# MainBoardRev2.net
KiCad netlist of a schematic drawn in EAGLE
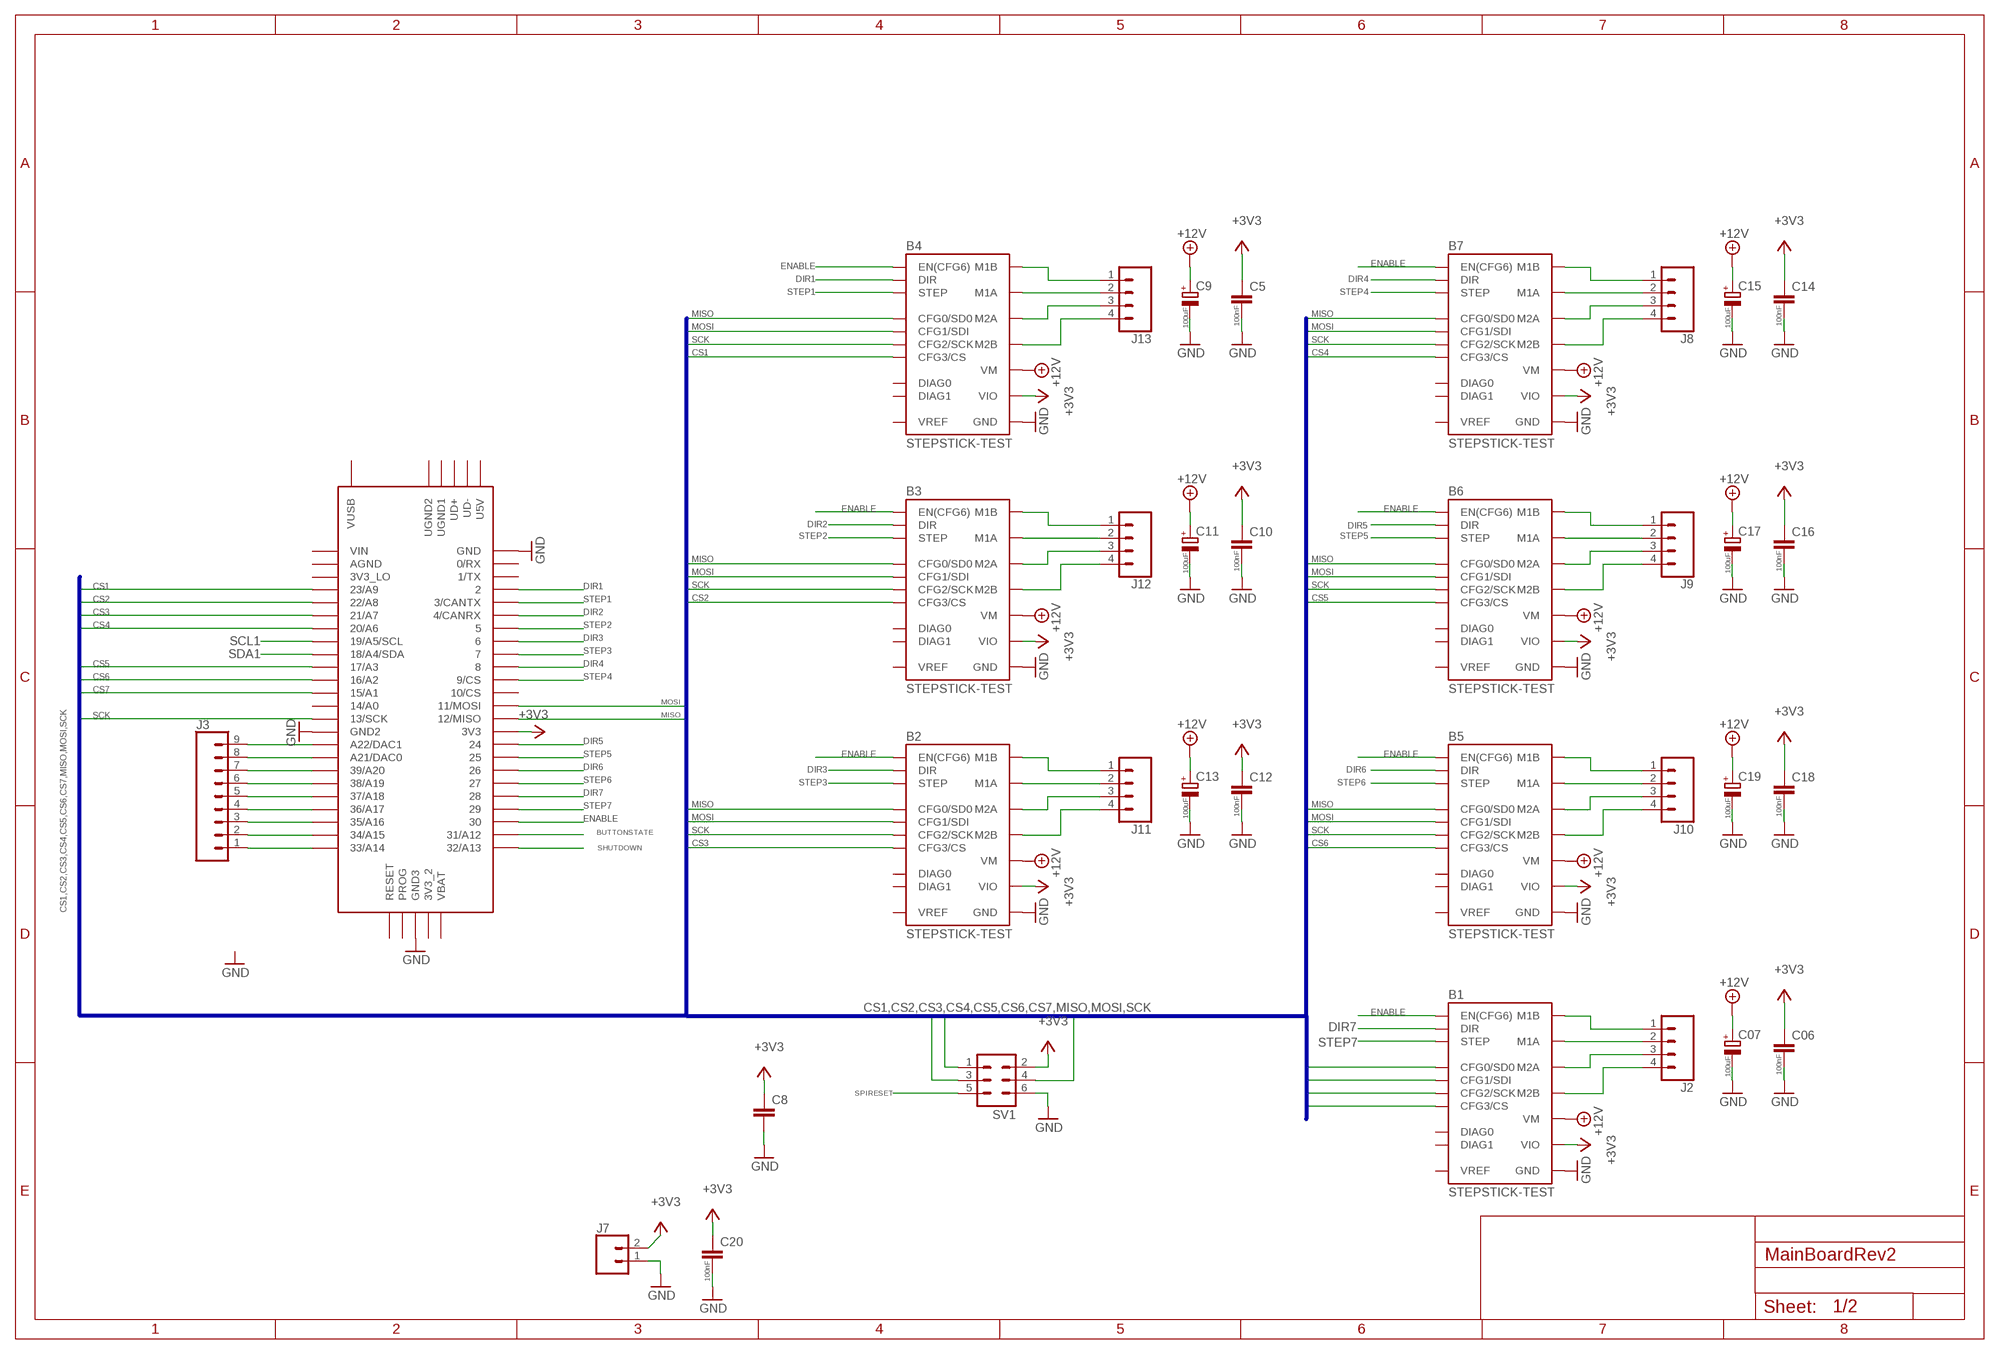
[diagram p0: schematic, sheet 1]
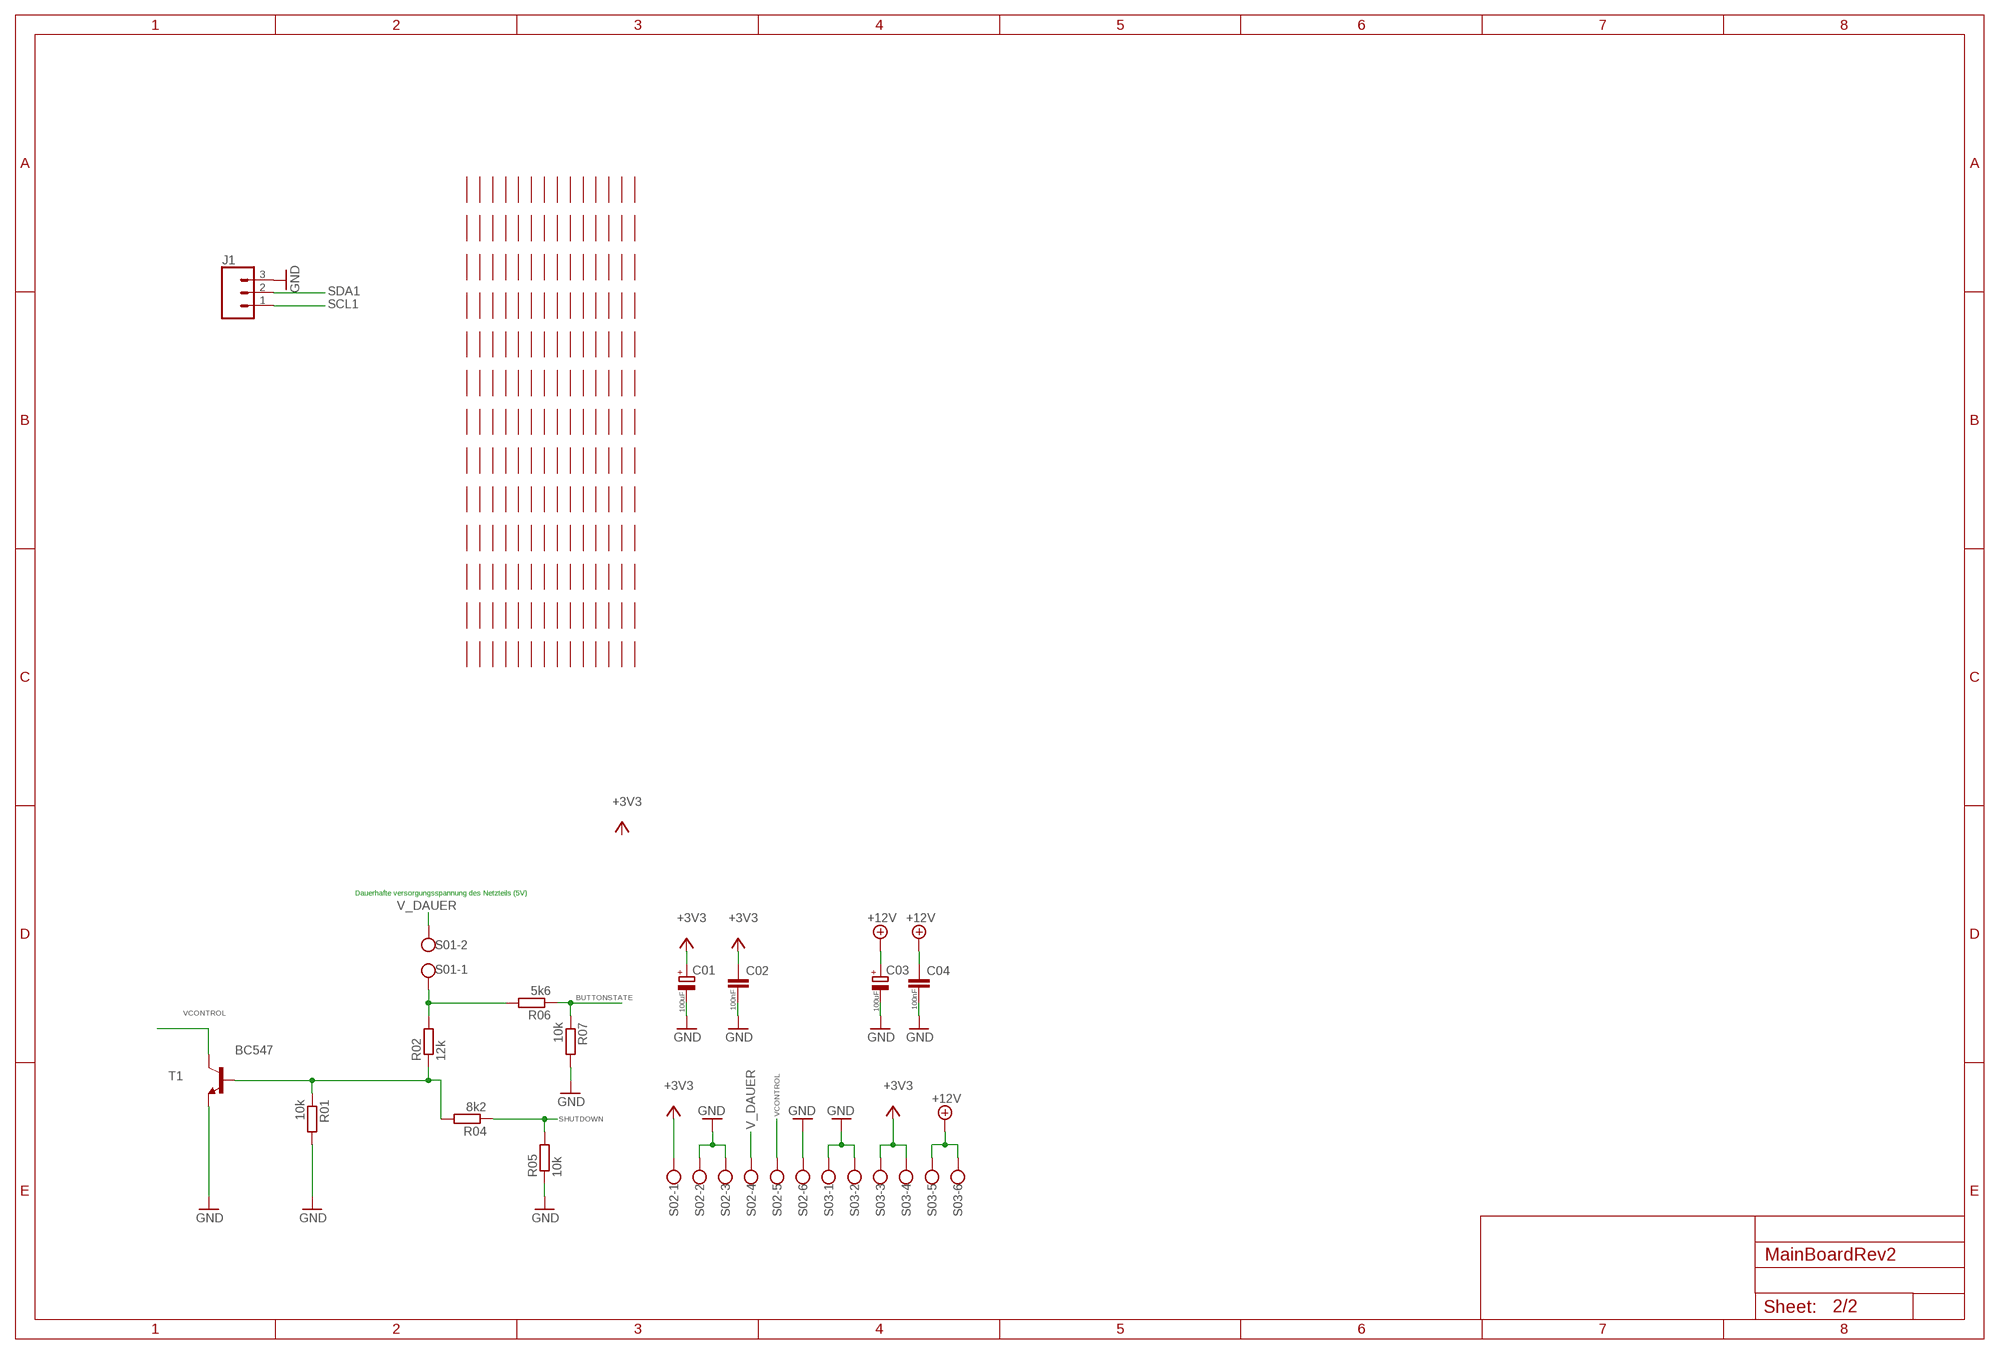
[diagram p1: schematic, sheet 2]

(export (version "E")
  (design (tool "Eeschema 10.0.6"))
  (components
    (comp (ref "C01")
      (value "100uF")
      (footprint "eagle-import:E2,5-6")
      (libsource (lib "eagle-import") (part "CPOL-EUE2.5-6"))
    )
    (comp (ref "C02")
      (value "100nF")
      (footprint "eagle-import:C050-024X044")
      (libsource (lib "eagle-import") (part "C-EU050-024X044"))
    )
    (comp (ref "C03")
      (value "100uF")
      (footprint "eagle-import:E2,5-6")
      (libsource (lib "eagle-import") (part "CPOL-EUE2.5-6"))
    )
    (comp (ref "C04")
      (value "100nF")
      (footprint "eagle-import:C050-024X044")
      (libsource (lib "eagle-import") (part "C-EU050-024X044"))
    )
    (comp (ref "J1")
      (value "CONN_03LONGPADS")
      (footprint "eagle-import:1X03_LONGPADS")
      (libsource (lib "eagle-import") (part "CONN_03LONGPADS"))
    )
    (comp (ref "R01")
      (value "10k")
      (footprint "eagle-import:0207_10")
      (libsource (lib "eagle-import") (part "R-EU_0207/10"))
    )
    (comp (ref "R02")
      (value "12k")
      (footprint "eagle-import:0207_10")
      (libsource (lib "eagle-import") (part "R-EU_0207/10"))
    )
    (comp (ref "R04")
      (value "8k2")
      (footprint "eagle-import:0207_10")
      (libsource (lib "eagle-import") (part "R-EU_0207/10"))
    )
    (comp (ref "R05")
      (value "10k")
      (footprint "eagle-import:0207_10")
      (libsource (lib "eagle-import") (part "R-EU_0207/10"))
    )
    (comp (ref "R06")
      (value "5k6")
      (footprint "eagle-import:0207_10")
      (libsource (lib "eagle-import") (part "R-EU_0207/10"))
    )
    (comp (ref "R07")
      (value "10k")
      (footprint "eagle-import:0207_10")
      (libsource (lib "eagle-import") (part "R-EU_0207/10"))
    )
    (comp (ref "S01")
      (value "W237-102")
      (footprint "eagle-import:W237-102")
      (fields (field (name "MPN") "237-102"))
      (libsource (lib "eagle-import") (part "W237-102"))
    )
    (comp (ref "S02")
      (value "W237-6")
      (footprint "eagle-import:W237-6")
      (libsource (lib "eagle-import") (part "W237-6"))
    )
    (comp (ref "S03")
      (value "W237-6")
      (footprint "eagle-import:W237-6")
      (libsource (lib "eagle-import") (part "W237-6"))
    )
    (comp (ref "T1")
      (value "BC547")
      (footprint "eagle-import:TO92")
      (libsource (lib "eagle-import") (part "BC547"))
    )
    (comp (ref "U$2")
      (value "LOCHRASTER")
      (footprint "eagle-import:LOCHRASTER")
      (libsource (lib "eagle-import") (part "LOCHRASTER"))
    )
    (comp (ref "B1")
      (value "STEPSTICK-TEST")
      (footprint "eagle-import:STEPSTICK-TEST")
      (libsource (lib "eagle-import") (part "STEPSTICK-TEST"))
    )
    (comp (ref "B2")
      (value "STEPSTICK-TEST")
      (footprint "eagle-import:STEPSTICK-TEST")
      (libsource (lib "eagle-import") (part "STEPSTICK-TEST"))
    )
    (comp (ref "B3")
      (value "STEPSTICK-TEST")
      (footprint "eagle-import:STEPSTICK-TEST")
      (libsource (lib "eagle-import") (part "STEPSTICK-TEST"))
    )
    (comp (ref "B4")
      (value "STEPSTICK-TEST")
      (footprint "eagle-import:STEPSTICK-TEST")
      (libsource (lib "eagle-import") (part "STEPSTICK-TEST"))
    )
    (comp (ref "B5")
      (value "STEPSTICK-TEST")
      (footprint "eagle-import:STEPSTICK-TEST")
      (libsource (lib "eagle-import") (part "STEPSTICK-TEST"))
    )
    (comp (ref "B6")
      (value "STEPSTICK-TEST")
      (footprint "eagle-import:STEPSTICK-TEST")
      (libsource (lib "eagle-import") (part "STEPSTICK-TEST"))
    )
    (comp (ref "B7")
      (value "STEPSTICK-TEST")
      (footprint "eagle-import:STEPSTICK-TEST")
      (libsource (lib "eagle-import") (part "STEPSTICK-TEST"))
    )
    (comp (ref "C5")
      (value "100nF")
      (footprint "eagle-import:C050-024X044")
      (libsource (lib "eagle-import") (part "C-EU050-024X044"))
    )
    (comp (ref "C06")
      (value "100nF")
      (footprint "eagle-import:C050-024X044")
      (libsource (lib "eagle-import") (part "C-EU050-024X044"))
    )
    (comp (ref "C07")
      (value "100uF")
      (footprint "eagle-import:E2,5-6")
      (libsource (lib "eagle-import") (part "CPOL-EUE2.5-6"))
    )
    (comp (ref "C8")
      (value "C-EU050-024X044")
      (footprint "eagle-import:C050-024X044")
      (libsource (lib "eagle-import") (part "C-EU050-024X044"))
    )
    (comp (ref "C9")
      (value "100uF")
      (footprint "eagle-import:E2,5-6")
      (libsource (lib "eagle-import") (part "CPOL-EUE2.5-6"))
    )
    (comp (ref "C10")
      (value "100nF")
      (footprint "eagle-import:C050-024X044")
      (libsource (lib "eagle-import") (part "C-EU050-024X044"))
    )
    (comp (ref "C11")
      (value "100uF")
      (footprint "eagle-import:E2,5-6")
      (libsource (lib "eagle-import") (part "CPOL-EUE2.5-6"))
    )
    (comp (ref "C12")
      (value "100nF")
      (footprint "eagle-import:C050-024X044")
      (libsource (lib "eagle-import") (part "C-EU050-024X044"))
    )
    (comp (ref "C13")
      (value "100uF")
      (footprint "eagle-import:E2,5-6")
      (libsource (lib "eagle-import") (part "CPOL-EUE2.5-6"))
    )
    (comp (ref "C14")
      (value "100nF")
      (footprint "eagle-import:C050-024X044")
      (libsource (lib "eagle-import") (part "C-EU050-024X044"))
    )
    (comp (ref "C15")
      (value "100uF")
      (footprint "eagle-import:E2,5-6")
      (libsource (lib "eagle-import") (part "CPOL-EUE2.5-6"))
    )
    (comp (ref "C16")
      (value "100nF")
      (footprint "eagle-import:C050-024X044")
      (libsource (lib "eagle-import") (part "C-EU050-024X044"))
    )
    (comp (ref "C17")
      (value "100uF")
      (footprint "eagle-import:E2,5-6")
      (libsource (lib "eagle-import") (part "CPOL-EUE2.5-6"))
    )
    (comp (ref "C18")
      (value "100nF")
      (footprint "eagle-import:C050-024X044")
      (libsource (lib "eagle-import") (part "C-EU050-024X044"))
    )
    (comp (ref "C19")
      (value "100uF")
      (footprint "eagle-import:E2,5-6")
      (libsource (lib "eagle-import") (part "CPOL-EUE2.5-6"))
    )
    (comp (ref "C20")
      (value "100nF")
      (footprint "eagle-import:C050-024X044")
      (libsource (lib "eagle-import") (part "C-EU050-024X044"))
    )
    (comp (ref "J2")
      (value "CONN_041X04_NO_SILK")
      (footprint "eagle-import:1X04_NO_SILK")
      (libsource (lib "eagle-import") (part "CONN_041X04_NO_SILK"))
    )
    (comp (ref "J3")
      (value "CONN_09LONGPADS")
      (footprint "eagle-import:1X09_LONGPADS")
      (libsource (lib "eagle-import") (part "CONN_09LONGPADS"))
    )
    (comp (ref "J7")
      (value "CONN_02PTH3")
      (footprint "eagle-import:1X02_LONGPADS")
      (libsource (lib "eagle-import") (part "CONN_02PTH3"))
    )
    (comp (ref "J8")
      (value "CONN_041X04_NO_SILK")
      (footprint "eagle-import:1X04_NO_SILK")
      (libsource (lib "eagle-import") (part "CONN_041X04_NO_SILK"))
    )
    (comp (ref "J9")
      (value "CONN_041X04_NO_SILK")
      (footprint "eagle-import:1X04_NO_SILK")
      (libsource (lib "eagle-import") (part "CONN_041X04_NO_SILK"))
    )
    (comp (ref "J10")
      (value "CONN_041X04_NO_SILK")
      (footprint "eagle-import:1X04_NO_SILK")
      (libsource (lib "eagle-import") (part "CONN_041X04_NO_SILK"))
    )
    (comp (ref "J11")
      (value "CONN_041X04_NO_SILK")
      (footprint "eagle-import:1X04_NO_SILK")
      (libsource (lib "eagle-import") (part "CONN_041X04_NO_SILK"))
    )
    (comp (ref "J12")
      (value "CONN_041X04_NO_SILK")
      (footprint "eagle-import:1X04_NO_SILK")
      (libsource (lib "eagle-import") (part "CONN_041X04_NO_SILK"))
    )
    (comp (ref "J13")
      (value "CONN_041X04_NO_SILK")
      (footprint "eagle-import:1X04_NO_SILK")
      (libsource (lib "eagle-import") (part "CONN_041X04_NO_SILK"))
    )
    (comp (ref "SV1")
      (value "MA03-2")
      (footprint "eagle-import:MA03-2")
      (libsource (lib "eagle-import") (part "MA03-2"))
    )
    (comp (ref "U$1")
      (value "TEENSY_4.1")
      (footprint "eagle-import:TEENSY_4.1")
      (libsource (lib "eagle-import") (part "TEENSY_4.1"))
    )
  )
  (nets
    (net (code "1") (name "+3V3") (class "Default")
      (node (ref "B1") (pin "VIO") (pinfunction "VIO_VIO") (pintype "power_in"))
      (node (ref "B2") (pin "VIO") (pinfunction "VIO_VIO") (pintype "power_in"))
      (node (ref "B3") (pin "VIO") (pinfunction "VIO_VIO") (pintype "power_in"))
      (node (ref "B4") (pin "VIO") (pinfunction "VIO_VIO") (pintype "power_in"))
      (node (ref "B5") (pin "VIO") (pinfunction "VIO_VIO") (pintype "power_in"))
      (node (ref "B6") (pin "VIO") (pinfunction "VIO_VIO") (pintype "power_in"))
      (node (ref "B7") (pin "VIO") (pinfunction "VIO_VIO") (pintype "power_in"))
      (node (ref "C01") (pin "+") (pinfunction "+_+") (pintype "passive"))
      (node (ref "C02") (pin "1") (pinfunction "1_1") (pintype "passive"))
      (node (ref "C06") (pin "1") (pinfunction "1_1") (pintype "passive"))
      (node (ref "C10") (pin "1") (pinfunction "1_1") (pintype "passive"))
      (node (ref "C12") (pin "1") (pinfunction "1_1") (pintype "passive"))
      (node (ref "C14") (pin "1") (pinfunction "1_1") (pintype "passive"))
      (node (ref "C16") (pin "1") (pinfunction "1_1") (pintype "passive"))
      (node (ref "C18") (pin "1") (pinfunction "1_1") (pintype "passive"))
      (node (ref "C20") (pin "1") (pinfunction "1_1") (pintype "passive"))
      (node (ref "C5") (pin "1") (pinfunction "1_1") (pintype "passive"))
      (node (ref "C8") (pin "1") (pinfunction "1_1") (pintype "passive"))
      (node (ref "J7") (pin "2") (pinfunction "2_2") (pintype "passive"))
      (node (ref "S02") (pin "1") (pinfunction "KL_1") (pintype "passive"))
      (node (ref "S03") (pin "3") (pinfunction "KL_3") (pintype "passive"))
      (node (ref "S03") (pin "4") (pinfunction "KL_4") (pintype "passive"))
      (node (ref "SV1") (pin "2") (pinfunction "2_2") (pintype "passive"))
      (node (ref "U$1") (pin "3V3") (pinfunction "3V3_3V3") (pintype "bidirectional"))
    )
    (net (code "2") (name "+12V") (class "Default")
      (node (ref "B1") (pin "VM") (pinfunction "VM_VM") (pintype "power_in"))
      (node (ref "B2") (pin "VM") (pinfunction "VM_VM") (pintype "power_in"))
      (node (ref "B3") (pin "VM") (pinfunction "VM_VM") (pintype "power_in"))
      (node (ref "B4") (pin "VM") (pinfunction "VM_VM") (pintype "power_in"))
      (node (ref "B5") (pin "VM") (pinfunction "VM_VM") (pintype "power_in"))
      (node (ref "B6") (pin "VM") (pinfunction "VM_VM") (pintype "power_in"))
      (node (ref "B7") (pin "VM") (pinfunction "VM_VM") (pintype "power_in"))
      (node (ref "C03") (pin "+") (pinfunction "+_+") (pintype "passive"))
      (node (ref "C04") (pin "1") (pinfunction "1_1") (pintype "passive"))
      (node (ref "C07") (pin "+") (pinfunction "+_+") (pintype "passive"))
      (node (ref "C11") (pin "+") (pinfunction "+_+") (pintype "passive"))
      (node (ref "C13") (pin "+") (pinfunction "+_+") (pintype "passive"))
      (node (ref "C15") (pin "+") (pinfunction "+_+") (pintype "passive"))
      (node (ref "C17") (pin "+") (pinfunction "+_+") (pintype "passive"))
      (node (ref "C19") (pin "+") (pinfunction "+_+") (pintype "passive"))
      (node (ref "C9") (pin "+") (pinfunction "+_+") (pintype "passive"))
      (node (ref "S03") (pin "5") (pinfunction "KL_5") (pintype "passive"))
      (node (ref "S03") (pin "6") (pinfunction "KL_6") (pintype "passive"))
    )
    (net (code "4") (name "BUTTONSTATE") (class "Default")
      (node (ref "R06") (pin "1") (pinfunction "1_1") (pintype "passive"))
      (node (ref "R07") (pin "1") (pinfunction "1_1") (pintype "passive"))
      (node (ref "U$1") (pin "31/A12") (pinfunction "31/A12_31/A12") (pintype "bidirectional"))
    )
    (net (code "5") (name "CS1") (class "Default")
      (node (ref "B4") (pin "CFG3") (pinfunction "CFG3/CS_CFG3") (pintype "bidirectional"))
      (node (ref "U$1") (pin "23/A9") (pinfunction "23/A9_23/A9") (pintype "bidirectional"))
    )
    (net (code "6") (name "CS2") (class "Default")
      (node (ref "B3") (pin "CFG3") (pinfunction "CFG3/CS_CFG3") (pintype "bidirectional"))
      (node (ref "U$1") (pin "22/A8") (pinfunction "22/A8_22/A8") (pintype "bidirectional"))
    )
    (net (code "7") (name "CS3") (class "Default")
      (node (ref "B2") (pin "CFG3") (pinfunction "CFG3/CS_CFG3") (pintype "bidirectional"))
      (node (ref "U$1") (pin "21/A7") (pinfunction "21/A7_21/A7") (pintype "bidirectional"))
    )
    (net (code "8") (name "CS4") (class "Default")
      (node (ref "B7") (pin "CFG3") (pinfunction "CFG3/CS_CFG3") (pintype "bidirectional"))
      (node (ref "U$1") (pin "20/A6") (pinfunction "20/A6_20/A6") (pintype "bidirectional"))
    )
    (net (code "9") (name "CS5") (class "Default")
      (node (ref "B6") (pin "CFG3") (pinfunction "CFG3/CS_CFG3") (pintype "bidirectional"))
      (node (ref "U$1") (pin "17/A3") (pinfunction "17/A3_17/A3") (pintype "bidirectional"))
    )
    (net (code "10") (name "CS6") (class "Default")
      (node (ref "B5") (pin "CFG3") (pinfunction "CFG3/CS_CFG3") (pintype "bidirectional"))
      (node (ref "U$1") (pin "16/A2") (pinfunction "16/A2_16/A2") (pintype "bidirectional"))
    )
    (net (code "11") (name "CS7") (class "Default")
      (node (ref "B1") (pin "CFG3") (pinfunction "CFG3/CS_CFG3") (pintype "bidirectional"))
      (node (ref "U$1") (pin "15/A1") (pinfunction "15/A1_15/A1") (pintype "bidirectional"))
    )
    (net (code "12") (name "DIR1") (class "Default")
      (node (ref "B4") (pin "DIR") (pinfunction "DIR_DIR") (pintype "bidirectional"))
      (node (ref "U$1") (pin "2") (pinfunction "2_2") (pintype "bidirectional"))
    )
    (net (code "13") (name "DIR2") (class "Default")
      (node (ref "B3") (pin "DIR") (pinfunction "DIR_DIR") (pintype "bidirectional"))
      (node (ref "U$1") (pin "4/CANRX") (pinfunction "4/CANRX_4/CANRX") (pintype "bidirectional"))
    )
    (net (code "14") (name "DIR3") (class "Default")
      (node (ref "B2") (pin "DIR") (pinfunction "DIR_DIR") (pintype "bidirectional"))
      (node (ref "U$1") (pin "6") (pinfunction "6_6") (pintype "bidirectional"))
    )
    (net (code "15") (name "DIR4") (class "Default")
      (node (ref "B7") (pin "DIR") (pinfunction "DIR_DIR") (pintype "bidirectional"))
      (node (ref "U$1") (pin "8") (pinfunction "8_8") (pintype "bidirectional"))
    )
    (net (code "16") (name "DIR5") (class "Default")
      (node (ref "B6") (pin "DIR") (pinfunction "DIR_DIR") (pintype "bidirectional"))
      (node (ref "U$1") (pin "24/A10") (pinfunction "24_24/A10") (pintype "bidirectional"))
    )
    (net (code "17") (name "DIR6") (class "Default")
      (node (ref "B5") (pin "DIR") (pinfunction "DIR_DIR") (pintype "bidirectional"))
      (node (ref "U$1") (pin "26/12") (pinfunction "26_26/12") (pintype "bidirectional"))
    )
    (net (code "18") (name "DIR7") (class "Default")
      (node (ref "B1") (pin "DIR") (pinfunction "DIR_DIR") (pintype "bidirectional"))
      (node (ref "U$1") (pin "28") (pinfunction "28_28") (pintype "bidirectional"))
    )
    (net (code "19") (name "ENABLE") (class "Default")
      (node (ref "B1") (pin "EN") (pinfunction "EN(CFG6)_EN") (pintype "bidirectional"))
      (node (ref "B2") (pin "EN") (pinfunction "EN(CFG6)_EN") (pintype "bidirectional"))
      (node (ref "B3") (pin "EN") (pinfunction "EN(CFG6)_EN") (pintype "bidirectional"))
      (node (ref "B4") (pin "EN") (pinfunction "EN(CFG6)_EN") (pintype "bidirectional"))
      (node (ref "B5") (pin "EN") (pinfunction "EN(CFG6)_EN") (pintype "bidirectional"))
      (node (ref "B6") (pin "EN") (pinfunction "EN(CFG6)_EN") (pintype "bidirectional"))
      (node (ref "B7") (pin "EN") (pinfunction "EN(CFG6)_EN") (pintype "bidirectional"))
      (node (ref "U$1") (pin "30") (pinfunction "30_30") (pintype "bidirectional"))
    )
    (net (code "20") (name "GND") (class "Default")
      (node (ref "B1") (pin "GND@1") (pinfunction "GND_GND@1") (pintype "power_in"))
      (node (ref "B1") (pin "GND@2") (pinfunction "GND_GND@2") (pintype "power_in"))
      (node (ref "B2") (pin "GND@1") (pinfunction "GND_GND@1") (pintype "power_in"))
      (node (ref "B2") (pin "GND@2") (pinfunction "GND_GND@2") (pintype "power_in"))
      (node (ref "B3") (pin "GND@1") (pinfunction "GND_GND@1") (pintype "power_in"))
      (node (ref "B3") (pin "GND@2") (pinfunction "GND_GND@2") (pintype "power_in"))
      (node (ref "B4") (pin "GND@1") (pinfunction "GND_GND@1") (pintype "power_in"))
      (node (ref "B4") (pin "GND@2") (pinfunction "GND_GND@2") (pintype "power_in"))
      (node (ref "B5") (pin "GND@1") (pinfunction "GND_GND@1") (pintype "power_in"))
      (node (ref "B5") (pin "GND@2") (pinfunction "GND_GND@2") (pintype "power_in"))
      (node (ref "B6") (pin "GND@1") (pinfunction "GND_GND@1") (pintype "power_in"))
      (node (ref "B6") (pin "GND@2") (pinfunction "GND_GND@2") (pintype "power_in"))
      (node (ref "B7") (pin "GND@1") (pinfunction "GND_GND@1") (pintype "power_in"))
      (node (ref "B7") (pin "GND@2") (pinfunction "GND_GND@2") (pintype "power_in"))
      (node (ref "C01") (pin "-") (pinfunction "-_-") (pintype "passive"))
      (node (ref "C02") (pin "2") (pinfunction "2_2") (pintype "passive"))
      (node (ref "C03") (pin "-") (pinfunction "-_-") (pintype "passive"))
      (node (ref "C04") (pin "2") (pinfunction "2_2") (pintype "passive"))
      (node (ref "C06") (pin "2") (pinfunction "2_2") (pintype "passive"))
      (node (ref "C07") (pin "-") (pinfunction "-_-") (pintype "passive"))
      (node (ref "C10") (pin "2") (pinfunction "2_2") (pintype "passive"))
      (node (ref "C11") (pin "-") (pinfunction "-_-") (pintype "passive"))
      (node (ref "C12") (pin "2") (pinfunction "2_2") (pintype "passive"))
      (node (ref "C13") (pin "-") (pinfunction "-_-") (pintype "passive"))
      (node (ref "C14") (pin "2") (pinfunction "2_2") (pintype "passive"))
      (node (ref "C15") (pin "-") (pinfunction "-_-") (pintype "passive"))
      (node (ref "C16") (pin "2") (pinfunction "2_2") (pintype "passive"))
      (node (ref "C17") (pin "-") (pinfunction "-_-") (pintype "passive"))
      (node (ref "C18") (pin "2") (pinfunction "2_2") (pintype "passive"))
      (node (ref "C19") (pin "-") (pinfunction "-_-") (pintype "passive"))
      (node (ref "C20") (pin "2") (pinfunction "2_2") (pintype "passive"))
      (node (ref "C5") (pin "2") (pinfunction "2_2") (pintype "passive"))
      (node (ref "C8") (pin "2") (pinfunction "2_2") (pintype "passive"))
      (node (ref "C9") (pin "-") (pinfunction "-_-") (pintype "passive"))
      (node (ref "J1") (pin "3") (pinfunction "3_3") (pintype "passive"))
      (node (ref "J7") (pin "1") (pinfunction "1_1") (pintype "passive"))
      (node (ref "R01") (pin "2") (pinfunction "2_2") (pintype "passive"))
      (node (ref "R05") (pin "1") (pinfunction "1_1") (pintype "passive"))
      (node (ref "R07") (pin "2") (pinfunction "2_2") (pintype "passive"))
      (node (ref "S02") (pin "2") (pinfunction "KL_2") (pintype "passive"))
      (node (ref "S02") (pin "3") (pinfunction "KL_3") (pintype "passive"))
      (node (ref "S02") (pin "6") (pinfunction "KL_6") (pintype "passive"))
      (node (ref "S03") (pin "1") (pinfunction "KL_1") (pintype "passive"))
      (node (ref "S03") (pin "2") (pinfunction "KL_2") (pintype "passive"))
      (node (ref "SV1") (pin "6") (pinfunction "6_6") (pintype "passive"))
      (node (ref "T1") (pin "1") (pinfunction "E_1") (pintype "passive"))
      (node (ref "U$1") (pin "GND") (pinfunction "GND_GND") (pintype "bidirectional"))
      (node (ref "U$1") (pin "GND2") (pinfunction "GND2_GND2") (pintype "bidirectional"))
      (node (ref "U$1") (pin "GND3") (pinfunction "GND3_GND3") (pintype "bidirectional"))
    )
    (net (code "21") (name "MISO") (class "Default")
      (node (ref "B1") (pin "NC/CFG0") (pinfunction "CFG0/SD0_NC/CFG0") (pintype "bidirectional"))
      (node (ref "B2") (pin "NC/CFG0") (pinfunction "CFG0/SD0_NC/CFG0") (pintype "bidirectional"))
      (node (ref "B3") (pin "NC/CFG0") (pinfunction "CFG0/SD0_NC/CFG0") (pintype "bidirectional"))
      (node (ref "B4") (pin "NC/CFG0") (pinfunction "CFG0/SD0_NC/CFG0") (pintype "bidirectional"))
      (node (ref "B5") (pin "NC/CFG0") (pinfunction "CFG0/SD0_NC/CFG0") (pintype "bidirectional"))
      (node (ref "B6") (pin "NC/CFG0") (pinfunction "CFG0/SD0_NC/CFG0") (pintype "bidirectional"))
      (node (ref "B7") (pin "NC/CFG0") (pinfunction "CFG0/SD0_NC/CFG0") (pintype "bidirectional"))
      (node (ref "SV1") (pin "1") (pinfunction "1_1") (pintype "passive"))
      (node (ref "U$1") (pin "12/MISO") (pinfunction "12/MISO_12/MISO") (pintype "bidirectional"))
    )
    (net (code "22") (name "MOSI") (class "Default")
      (node (ref "B1") (pin "CFG1") (pinfunction "CFG1/SDI_CFG1") (pintype "bidirectional"))
      (node (ref "B2") (pin "CFG1") (pinfunction "CFG1/SDI_CFG1") (pintype "bidirectional"))
      (node (ref "B3") (pin "CFG1") (pinfunction "CFG1/SDI_CFG1") (pintype "bidirectional"))
      (node (ref "B4") (pin "CFG1") (pinfunction "CFG1/SDI_CFG1") (pintype "bidirectional"))
      (node (ref "B5") (pin "CFG1") (pinfunction "CFG1/SDI_CFG1") (pintype "bidirectional"))
      (node (ref "B6") (pin "CFG1") (pinfunction "CFG1/SDI_CFG1") (pintype "bidirectional"))
      (node (ref "B7") (pin "CFG1") (pinfunction "CFG1/SDI_CFG1") (pintype "bidirectional"))
      (node (ref "SV1") (pin "4") (pinfunction "4_4") (pintype "passive"))
      (node (ref "U$1") (pin "11/MOSI") (pinfunction "11/MOSI_11/MOSI") (pintype "bidirectional"))
    )
    (net (code "23") (name "Net-(B1-PadM1A)") (class "Default")
      (node (ref "B1") (pin "M1A") (pinfunction "M1A_M1A") (pintype "output"))
      (node (ref "J2") (pin "2") (pinfunction "2_2") (pintype "passive"))
    )
    (net (code "24") (name "Net-(B1-PadM1B)") (class "Default")
      (node (ref "B1") (pin "M1B") (pinfunction "M1B_M1B") (pintype "output"))
      (node (ref "J2") (pin "1") (pinfunction "1_1") (pintype "passive"))
    )
    (net (code "25") (name "Net-(B1-PadM2A)") (class "Default")
      (node (ref "B1") (pin "M2A") (pinfunction "M2A_M2A") (pintype "output"))
      (node (ref "J2") (pin "3") (pinfunction "3_3") (pintype "passive"))
    )
    (net (code "26") (name "Net-(B1-PadM2B)") (class "Default")
      (node (ref "B1") (pin "M2B") (pinfunction "M2B_M2B") (pintype "output"))
      (node (ref "J2") (pin "4") (pinfunction "4_4") (pintype "passive"))
    )
    (net (code "27") (name "Net-(B2-PadM1A)") (class "Default")
      (node (ref "B2") (pin "M1A") (pinfunction "M1A_M1A") (pintype "output"))
      (node (ref "J11") (pin "2") (pinfunction "2_2") (pintype "passive"))
    )
    (net (code "28") (name "Net-(B2-PadM1B)") (class "Default")
      (node (ref "B2") (pin "M1B") (pinfunction "M1B_M1B") (pintype "output"))
      (node (ref "J11") (pin "1") (pinfunction "1_1") (pintype "passive"))
    )
    (net (code "29") (name "Net-(B2-PadM2A)") (class "Default")
      (node (ref "B2") (pin "M2A") (pinfunction "M2A_M2A") (pintype "output"))
      (node (ref "J11") (pin "3") (pinfunction "3_3") (pintype "passive"))
    )
    (net (code "30") (name "Net-(B2-PadM2B)") (class "Default")
      (node (ref "B2") (pin "M2B") (pinfunction "M2B_M2B") (pintype "output"))
      (node (ref "J11") (pin "4") (pinfunction "4_4") (pintype "passive"))
    )
    (net (code "31") (name "Net-(B3-PadM1A)") (class "Default")
      (node (ref "B3") (pin "M1A") (pinfunction "M1A_M1A") (pintype "output"))
      (node (ref "J12") (pin "2") (pinfunction "2_2") (pintype "passive"))
    )
    (net (code "32") (name "Net-(B3-PadM1B)") (class "Default")
      (node (ref "B3") (pin "M1B") (pinfunction "M1B_M1B") (pintype "output"))
      (node (ref "J12") (pin "1") (pinfunction "1_1") (pintype "passive"))
    )
    (net (code "33") (name "Net-(B3-PadM2A)") (class "Default")
      (node (ref "B3") (pin "M2A") (pinfunction "M2A_M2A") (pintype "output"))
      (node (ref "J12") (pin "3") (pinfunction "3_3") (pintype "passive"))
    )
    (net (code "34") (name "Net-(B3-PadM2B)") (class "Default")
      (node (ref "B3") (pin "M2B") (pinfunction "M2B_M2B") (pintype "output"))
      (node (ref "J12") (pin "4") (pinfunction "4_4") (pintype "passive"))
    )
    (net (code "35") (name "Net-(B4-PadM1A)") (class "Default")
      (node (ref "B4") (pin "M1A") (pinfunction "M1A_M1A") (pintype "output"))
      (node (ref "J13") (pin "2") (pinfunction "2_2") (pintype "passive"))
    )
    (net (code "36") (name "Net-(B4-PadM1B)") (class "Default")
      (node (ref "B4") (pin "M1B") (pinfunction "M1B_M1B") (pintype "output"))
      (node (ref "J13") (pin "1") (pinfunction "1_1") (pintype "passive"))
    )
    (net (code "37") (name "Net-(B4-PadM2A)") (class "Default")
      (node (ref "B4") (pin "M2A") (pinfunction "M2A_M2A") (pintype "output"))
      (node (ref "J13") (pin "3") (pinfunction "3_3") (pintype "passive"))
    )
    (net (code "38") (name "Net-(B4-PadM2B)") (class "Default")
      (node (ref "B4") (pin "M2B") (pinfunction "M2B_M2B") (pintype "output"))
      (node (ref "J13") (pin "4") (pinfunction "4_4") (pintype "passive"))
    )
    (net (code "39") (name "Net-(B5-PadM1A)") (class "Default")
      (node (ref "B5") (pin "M1A") (pinfunction "M1A_M1A") (pintype "output"))
      (node (ref "J10") (pin "2") (pinfunction "2_2") (pintype "passive"))
    )
    (net (code "40") (name "Net-(B5-PadM1B)") (class "Default")
      (node (ref "B5") (pin "M1B") (pinfunction "M1B_M1B") (pintype "output"))
      (node (ref "J10") (pin "1") (pinfunction "1_1") (pintype "passive"))
    )
    (net (code "41") (name "Net-(B5-PadM2A)") (class "Default")
      (node (ref "B5") (pin "M2A") (pinfunction "M2A_M2A") (pintype "output"))
      (node (ref "J10") (pin "3") (pinfunction "3_3") (pintype "passive"))
    )
    (net (code "42") (name "Net-(B5-PadM2B)") (class "Default")
      (node (ref "B5") (pin "M2B") (pinfunction "M2B_M2B") (pintype "output"))
      (node (ref "J10") (pin "4") (pinfunction "4_4") (pintype "passive"))
    )
    (net (code "43") (name "Net-(B6-PadM1A)") (class "Default")
      (node (ref "B6") (pin "M1A") (pinfunction "M1A_M1A") (pintype "output"))
      (node (ref "J9") (pin "2") (pinfunction "2_2") (pintype "passive"))
    )
    (net (code "44") (name "Net-(B6-PadM1B)") (class "Default")
      (node (ref "B6") (pin "M1B") (pinfunction "M1B_M1B") (pintype "output"))
      (node (ref "J9") (pin "1") (pinfunction "1_1") (pintype "passive"))
    )
    (net (code "45") (name "Net-(B6-PadM2A)") (class "Default")
      (node (ref "B6") (pin "M2A") (pinfunction "M2A_M2A") (pintype "output"))
      (node (ref "J9") (pin "3") (pinfunction "3_3") (pintype "passive"))
    )
    (net (code "46") (name "Net-(B6-PadM2B)") (class "Default")
      (node (ref "B6") (pin "M2B") (pinfunction "M2B_M2B") (pintype "output"))
      (node (ref "J9") (pin "4") (pinfunction "4_4") (pintype "passive"))
    )
    (net (code "47") (name "Net-(B7-PadM1A)") (class "Default")
      (node (ref "B7") (pin "M1A") (pinfunction "M1A_M1A") (pintype "output"))
      (node (ref "J8") (pin "2") (pinfunction "2_2") (pintype "passive"))
    )
    (net (code "48") (name "Net-(B7-PadM1B)") (class "Default")
      (node (ref "B7") (pin "M1B") (pinfunction "M1B_M1B") (pintype "output"))
      (node (ref "J8") (pin "1") (pinfunction "1_1") (pintype "passive"))
    )
    (net (code "49") (name "Net-(B7-PadM2A)") (class "Default")
      (node (ref "B7") (pin "M2A") (pinfunction "M2A_M2A") (pintype "output"))
      (node (ref "J8") (pin "3") (pinfunction "3_3") (pintype "passive"))
    )
    (net (code "50") (name "Net-(B7-PadM2B)") (class "Default")
      (node (ref "B7") (pin "M2B") (pinfunction "M2B_M2B") (pintype "output"))
      (node (ref "J8") (pin "4") (pinfunction "4_4") (pintype "passive"))
    )
    (net (code "51") (name "Net-(J3-Pad1)") (class "Default")
      (node (ref "J3") (pin "1") (pinfunction "1_1") (pintype "passive"))
      (node (ref "U$1") (pin "33/A14") (pinfunction "33/A14_33/A14") (pintype "bidirectional"))
    )
    (net (code "52") (name "Net-(J3-Pad2)") (class "Default")
      (node (ref "J3") (pin "2") (pinfunction "2_2") (pintype "passive"))
      (node (ref "U$1") (pin "34/A15") (pinfunction "34/A15_34/A15") (pintype "bidirectional"))
    )
    (net (code "53") (name "Net-(J3-Pad3)") (class "Default")
      (node (ref "J3") (pin "3") (pinfunction "3_3") (pintype "passive"))
      (node (ref "U$1") (pin "35/A16") (pinfunction "35/A16_35/A16") (pintype "bidirectional"))
    )
    (net (code "54") (name "Net-(J3-Pad4)") (class "Default")
      (node (ref "J3") (pin "4") (pinfunction "4_4") (pintype "passive"))
      (node (ref "U$1") (pin "36/A17") (pinfunction "36/A17_36/A17") (pintype "bidirectional"))
    )
    (net (code "55") (name "Net-(J3-Pad5)") (class "Default")
      (node (ref "J3") (pin "5") (pinfunction "5_5") (pintype "passive"))
      (node (ref "U$1") (pin "37/A18") (pinfunction "37/A18_37/A18") (pintype "bidirectional"))
    )
    (net (code "56") (name "Net-(J3-Pad6)") (class "Default")
      (node (ref "J3") (pin "6") (pinfunction "6_6") (pintype "passive"))
      (node (ref "U$1") (pin "38/A19") (pinfunction "38/A19_38/A19") (pintype "bidirectional"))
    )
    (net (code "57") (name "Net-(J3-Pad7)") (class "Default")
      (node (ref "J3") (pin "7") (pinfunction "7_7") (pintype "passive"))
      (node (ref "U$1") (pin "39/A20") (pinfunction "39/A20_39/A20") (pintype "bidirectional"))
    )
    (net (code "58") (name "Net-(J3-Pad9)") (class "Default")
      (node (ref "J3") (pin "9") (pinfunction "9_9") (pintype "passive"))
      (node (ref "U$1") (pin "A22/DAC1") (pinfunction "A22/DAC1_A22/DAC1") (pintype "bidirectional"))
    )
    (net (code "59") (name "Net-(S01A-KL)") (class "Default")
      (node (ref "R02") (pin "2") (pinfunction "2_2") (pintype "passive"))
      (node (ref "R06") (pin "2") (pinfunction "2_2") (pintype "passive"))
      (node (ref "S01") (pin "1") (pinfunction "KL_1") (pintype "passive"))
    )
    (net (code "60") (name "Net-(T1-B)") (class "Default")
      (node (ref "R01") (pin "1") (pinfunction "1_1") (pintype "passive"))
      (node (ref "R02") (pin "1") (pinfunction "1_1") (pintype "passive"))
      (node (ref "R04") (pin "2") (pinfunction "2_2") (pintype "passive"))
      (node (ref "T1") (pin "2") (pinfunction "B_2") (pintype "passive"))
    )
    (net (code "61") (name "Net-(U$1-A21{slash}DAC0)") (class "Default")
      (node (ref "J3") (pin "8") (pinfunction "8_8") (pintype "passive"))
      (node (ref "U$1") (pin "21/DAC0") (pinfunction "A21/DAC0_21/DAC0") (pintype "bidirectional"))
    )
    (net (code "62") (name "SCK") (class "Default")
      (node (ref "B1") (pin "CFG2") (pinfunction "CFG2/SCK_CFG2") (pintype "bidirectional"))
      (node (ref "B2") (pin "CFG2") (pinfunction "CFG2/SCK_CFG2") (pintype "bidirectional"))
      (node (ref "B3") (pin "CFG2") (pinfunction "CFG2/SCK_CFG2") (pintype "bidirectional"))
      (node (ref "B4") (pin "CFG2") (pinfunction "CFG2/SCK_CFG2") (pintype "bidirectional"))
      (node (ref "B5") (pin "CFG2") (pinfunction "CFG2/SCK_CFG2") (pintype "bidirectional"))
      (node (ref "B6") (pin "CFG2") (pinfunction "CFG2/SCK_CFG2") (pintype "bidirectional"))
      (node (ref "B7") (pin "CFG2") (pinfunction "CFG2/SCK_CFG2") (pintype "bidirectional"))
      (node (ref "SV1") (pin "3") (pinfunction "3_3") (pintype "passive"))
      (node (ref "U$1") (pin "13/SCK") (pinfunction "13/SCK_13/SCK") (pintype "bidirectional"))
    )
    (net (code "63") (name "SCL1") (class "Default")
      (node (ref "J1") (pin "1") (pinfunction "1_1") (pintype "passive"))
      (node (ref "U$1") (pin "19/A5/SCL") (pinfunction "19/A5/SCL_19/A5/SCL") (pintype "bidirectional"))
    )
    (net (code "64") (name "SDA1") (class "Default")
      (node (ref "J1") (pin "2") (pinfunction "2_2") (pintype "passive"))
      (node (ref "U$1") (pin "18/A4/SDA") (pinfunction "18/A4/SDA_18/A4/SDA") (pintype "bidirectional"))
    )
    (net (code "65") (name "SHUTDOWN") (class "Default")
      (node (ref "R04") (pin "1") (pinfunction "1_1") (pintype "passive"))
      (node (ref "R05") (pin "2") (pinfunction "2_2") (pintype "passive"))
      (node (ref "U$1") (pin "32/A13") (pinfunction "32/A13_32/A13") (pintype "bidirectional"))
    )
    (net (code "66") (name "SPIRESET") (class "Default")
      (node (ref "SV1") (pin "5") (pinfunction "5_5") (pintype "passive"))
    )
    (net (code "67") (name "STEP1") (class "Default")
      (node (ref "B4") (pin "STEP") (pinfunction "STEP_STEP") (pintype "bidirectional"))
      (node (ref "U$1") (pin "3/CANTX") (pinfunction "3/CANTX_3/CANTX") (pintype "bidirectional"))
    )
    (net (code "68") (name "STEP2") (class "Default")
      (node (ref "B3") (pin "STEP") (pinfunction "STEP_STEP") (pintype "bidirectional"))
      (node (ref "U$1") (pin "5") (pinfunction "5_5") (pintype "bidirectional"))
    )
    (net (code "69") (name "STEP3") (class "Default")
      (node (ref "B2") (pin "STEP") (pinfunction "STEP_STEP") (pintype "bidirectional"))
      (node (ref "U$1") (pin "7") (pinfunction "7_7") (pintype "bidirectional"))
    )
    (net (code "70") (name "STEP4") (class "Default")
      (node (ref "B7") (pin "STEP") (pinfunction "STEP_STEP") (pintype "bidirectional"))
      (node (ref "U$1") (pin "9/CS") (pinfunction "9/CS_9/CS") (pintype "bidirectional"))
    )
    (net (code "71") (name "STEP5") (class "Default")
      (node (ref "B6") (pin "STEP") (pinfunction "STEP_STEP") (pintype "bidirectional"))
      (node (ref "U$1") (pin "25/A11") (pinfunction "25_25/A11") (pintype "bidirectional"))
    )
    (net (code "72") (name "STEP6") (class "Default")
      (node (ref "B5") (pin "STEP") (pinfunction "STEP_STEP") (pintype "bidirectional"))
      (node (ref "U$1") (pin "27/A13") (pinfunction "27_27/A13") (pintype "bidirectional"))
    )
    (net (code "73") (name "STEP7") (class "Default")
      (node (ref "B1") (pin "STEP") (pinfunction "STEP_STEP") (pintype "bidirectional"))
      (node (ref "U$1") (pin "29") (pinfunction "29_29") (pintype "bidirectional"))
    )
    (net (code "74") (name "VCONTROL") (class "Default")
      (node (ref "S02") (pin "5") (pinfunction "KL_5") (pintype "passive"))
      (node (ref "T1") (pin "3") (pinfunction "C_3") (pintype "passive"))
    )
    (net (code "75") (name "V_DAUER") (class "Default")
      (node (ref "S01") (pin "2") (pinfunction "KL_2") (pintype "passive"))
      (node (ref "S02") (pin "4") (pinfunction "KL_4") (pintype "passive"))
    )
    (net (code "76") (name "unconnected-(B1-PadDIAG0)") (class "Default")
      (node (ref "B1") (pin "DIAG0") (pinfunction "DIAG0_DIAG0") (pintype "bidirectional"))
    )
    (net (code "77") (name "unconnected-(B1-PadDIAG1)") (class "Default")
      (node (ref "B1") (pin "DIAG1") (pinfunction "DIAG1_DIAG1") (pintype "bidirectional"))
    )
    (net (code "78") (name "unconnected-(B1-PadVREF)") (class "Default")
      (node (ref "B1") (pin "VREF") (pinfunction "VREF_VREF") (pintype "passive"))
    )
    (net (code "79") (name "unconnected-(B2-PadDIAG0)") (class "Default")
      (node (ref "B2") (pin "DIAG0") (pinfunction "DIAG0_DIAG0") (pintype "bidirectional"))
    )
    (net (code "80") (name "unconnected-(B2-PadDIAG1)") (class "Default")
      (node (ref "B2") (pin "DIAG1") (pinfunction "DIAG1_DIAG1") (pintype "bidirectional"))
    )
    (net (code "81") (name "unconnected-(B2-PadVREF)") (class "Default")
      (node (ref "B2") (pin "VREF") (pinfunction "VREF_VREF") (pintype "passive"))
    )
    (net (code "82") (name "unconnected-(B3-PadDIAG0)") (class "Default")
      (node (ref "B3") (pin "DIAG0") (pinfunction "DIAG0_DIAG0") (pintype "bidirectional"))
    )
    (net (code "83") (name "unconnected-(B3-PadDIAG1)") (class "Default")
      (node (ref "B3") (pin "DIAG1") (pinfunction "DIAG1_DIAG1") (pintype "bidirectional"))
    )
    (net (code "84") (name "unconnected-(B3-PadVREF)") (class "Default")
      (node (ref "B3") (pin "VREF") (pinfunction "VREF_VREF") (pintype "passive"))
    )
    (net (code "85") (name "unconnected-(B4-PadDIAG0)") (class "Default")
      (node (ref "B4") (pin "DIAG0") (pinfunction "DIAG0_DIAG0") (pintype "bidirectional"))
    )
    (net (code "86") (name "unconnected-(B4-PadDIAG1)") (class "Default")
      (node (ref "B4") (pin "DIAG1") (pinfunction "DIAG1_DIAG1") (pintype "bidirectional"))
    )
    (net (code "87") (name "unconnected-(B4-PadVREF)") (class "Default")
      (node (ref "B4") (pin "VREF") (pinfunction "VREF_VREF") (pintype "passive"))
    )
    (net (code "88") (name "unconnected-(B5-PadDIAG0)") (class "Default")
      (node (ref "B5") (pin "DIAG0") (pinfunction "DIAG0_DIAG0") (pintype "bidirectional"))
    )
    (net (code "89") (name "unconnected-(B5-PadDIAG1)") (class "Default")
      (node (ref "B5") (pin "DIAG1") (pinfunction "DIAG1_DIAG1") (pintype "bidirectional"))
    )
    (net (code "90") (name "unconnected-(B5-PadVREF)") (class "Default")
      (node (ref "B5") (pin "VREF") (pinfunction "VREF_VREF") (pintype "passive"))
    )
    (net (code "91") (name "unconnected-(B6-PadDIAG0)") (class "Default")
      (node (ref "B6") (pin "DIAG0") (pinfunction "DIAG0_DIAG0") (pintype "bidirectional"))
    )
    (net (code "92") (name "unconnected-(B6-PadDIAG1)") (class "Default")
      (node (ref "B6") (pin "DIAG1") (pinfunction "DIAG1_DIAG1") (pintype "bidirectional"))
    )
    (net (code "93") (name "unconnected-(B6-PadVREF)") (class "Default")
      (node (ref "B6") (pin "VREF") (pinfunction "VREF_VREF") (pintype "passive"))
    )
    (net (code "94") (name "unconnected-(B7-PadDIAG0)") (class "Default")
      (node (ref "B7") (pin "DIAG0") (pinfunction "DIAG0_DIAG0") (pintype "bidirectional"))
    )
    (net (code "95") (name "unconnected-(B7-PadDIAG1)") (class "Default")
      (node (ref "B7") (pin "DIAG1") (pinfunction "DIAG1_DIAG1") (pintype "bidirectional"))
    )
    (net (code "96") (name "unconnected-(B7-PadVREF)") (class "Default")
      (node (ref "B7") (pin "VREF") (pinfunction "VREF_VREF") (pintype "passive"))
    )
    (net (code "97") (name "unconnected-(U$1-Pad0{slash}RX)") (class "Default")
      (node (ref "U$1") (pin "0/RX") (pinfunction "0/RX_0/RX") (pintype "bidirectional"))
    )
    (net (code "98") (name "unconnected-(U$1-Pad1{slash}TX)") (class "Default")
      (node (ref "U$1") (pin "1/TX") (pinfunction "1/TX_1/TX") (pintype "bidirectional"))
    )
    (net (code "99") (name "unconnected-(U$1-Pad3V3_2)") (class "Default")
      (node (ref "U$1") (pin "3V3_2") (pinfunction "3V3_2_3V3_2") (pintype "bidirectional"))
    )
    (net (code "100") (name "unconnected-(U$1-Pad3V3_LO)") (class "Default")
      (node (ref "U$1") (pin "3V3_LO") (pinfunction "3V3_LO_3V3_LO") (pintype "bidirectional"))
    )
    (net (code "101") (name "unconnected-(U$1-Pad10{slash}CS)") (class "Default")
      (node (ref "U$1") (pin "10/CS") (pinfunction "10/CS_10/CS") (pintype "bidirectional"))
    )
    (net (code "102") (name "unconnected-(U$1-Pad14{slash}A0)") (class "Default")
      (node (ref "U$1") (pin "14/A0") (pinfunction "14/A0_14/A0") (pintype "bidirectional"))
    )
    (net (code "103") (name "unconnected-(U$1-PadAGND)") (class "Default")
      (node (ref "U$1") (pin "AGND") (pinfunction "AGND_AGND") (pintype "bidirectional"))
    )
    (net (code "104") (name "unconnected-(U$1-PadPROG)") (class "Default")
      (node (ref "U$1") (pin "PROG") (pinfunction "PROG_PROG") (pintype "bidirectional"))
    )
    (net (code "105") (name "unconnected-(U$1-PadRESET)") (class "Default")
      (node (ref "U$1") (pin "RESET") (pinfunction "RESET_RESET") (pintype "bidirectional"))
    )
    (net (code "106") (name "unconnected-(U$1-PadU5V)") (class "Default")
      (node (ref "U$1") (pin "U5V") (pinfunction "U5V_U5V") (pintype "bidirectional"))
    )
    (net (code "107") (name "unconnected-(U$1-PadUD+)") (class "Default")
      (node (ref "U$1") (pin "UD+") (pinfunction "UD+_UD+") (pintype "bidirectional"))
    )
    (net (code "108") (name "unconnected-(U$1-PadUD-)") (class "Default")
      (node (ref "U$1") (pin "UD-") (pinfunction "UD-_UD-") (pintype "bidirectional"))
    )
    (net (code "109") (name "unconnected-(U$1-PadUGND1)") (class "Default")
      (node (ref "U$1") (pin "UGND1") (pinfunction "UGND1_UGND1") (pintype "bidirectional"))
    )
    (net (code "110") (name "unconnected-(U$1-PadUGND2)") (class "Default")
      (node (ref "U$1") (pin "UGND2") (pinfunction "UGND2_UGND2") (pintype "bidirectional"))
    )
    (net (code "111") (name "unconnected-(U$1-PadVBAT)") (class "Default")
      (node (ref "U$1") (pin "VBAT") (pinfunction "VBAT_VBAT") (pintype "bidirectional"))
    )
    (net (code "112") (name "unconnected-(U$1-PadVIN)") (class "Default")
      (node (ref "U$1") (pin "VIN") (pinfunction "VIN_VIN") (pintype "bidirectional"))
    )
    (net (code "113") (name "unconnected-(U$1-PadVUSB)") (class "Default")
      (node (ref "U$1") (pin "VUSB") (pinfunction "VUSB_VUSB") (pintype "bidirectional"))
    )
    (net (code "114") (name "unconnected-(U$2-PadP$1)") (class "Default")
      (node (ref "U$2") (pin "P$1") (pinfunction "P$1_P$1") (pintype "bidirectional"))
    )
    (net (code "115") (name "unconnected-(U$2-PadP$2)") (class "Default")
      (node (ref "U$2") (pin "P$2") (pinfunction "P$2_P$2") (pintype "bidirectional"))
    )
    (net (code "116") (name "unconnected-(U$2-PadP$3)") (class "Default")
      (node (ref "U$2") (pin "P$3") (pinfunction "P$3_P$3") (pintype "bidirectional"))
    )
    (net (code "117") (name "unconnected-(U$2-PadP$4)") (class "Default")
      (node (ref "U$2") (pin "P$4") (pinfunction "P$4_P$4") (pintype "bidirectional"))
    )
    (net (code "118") (name "unconnected-(U$2-PadP$5)") (class "Default")
      (node (ref "U$2") (pin "P$5") (pinfunction "P$5_P$5") (pintype "bidirectional"))
    )
    (net (code "119") (name "unconnected-(U$2-PadP$6)") (class "Default")
      (node (ref "U$2") (pin "P$6") (pinfunction "P$6_P$6") (pintype "bidirectional"))
    )
    (net (code "120") (name "unconnected-(U$2-PadP$7)") (class "Default")
      (node (ref "U$2") (pin "P$7") (pinfunction "P$7_P$7") (pintype "bidirectional"))
    )
    (net (code "121") (name "unconnected-(U$2-PadP$8)") (class "Default")
      (node (ref "U$2") (pin "P$8") (pinfunction "P$8_P$8") (pintype "bidirectional"))
    )
    (net (code "122") (name "unconnected-(U$2-PadP$9)") (class "Default")
      (node (ref "U$2") (pin "P$9") (pinfunction "P$9_P$9") (pintype "bidirectional"))
    )
    (net (code "123") (name "unconnected-(U$2-PadP$10)") (class "Default")
      (node (ref "U$2") (pin "P$10") (pinfunction "P$10_P$10") (pintype "bidirectional"))
    )
    (net (code "124") (name "unconnected-(U$2-PadP$11)") (class "Default")
      (node (ref "U$2") (pin "P$11") (pinfunction "P$11_P$11") (pintype "bidirectional"))
    )
    (net (code "125") (name "unconnected-(U$2-PadP$12)") (class "Default")
      (node (ref "U$2") (pin "P$12") (pinfunction "P$12_P$12") (pintype "bidirectional"))
    )
    (net (code "126") (name "unconnected-(U$2-PadP$13)") (class "Default")
      (node (ref "U$2") (pin "P$13") (pinfunction "P$13_P$13") (pintype "bidirectional"))
    )
    (net (code "127") (name "unconnected-(U$2-PadP$14)") (class "Default")
      (node (ref "U$2") (pin "P$14") (pinfunction "P$14_P$14") (pintype "bidirectional"))
    )
    (net (code "128") (name "unconnected-(U$2-PadP$15)") (class "Default")
      (node (ref "U$2") (pin "P$15") (pinfunction "P$15_P$15") (pintype "bidirectional"))
    )
    (net (code "129") (name "unconnected-(U$2-PadP$16)") (class "Default")
      (node (ref "U$2") (pin "P$16") (pinfunction "P$16_P$16") (pintype "bidirectional"))
    )
    (net (code "130") (name "unconnected-(U$2-PadP$17)") (class "Default")
      (node (ref "U$2") (pin "P$17") (pinfunction "P$17_P$17") (pintype "bidirectional"))
    )
    (net (code "131") (name "unconnected-(U$2-PadP$18)") (class "Default")
      (node (ref "U$2") (pin "P$18") (pinfunction "P$18_P$18") (pintype "bidirectional"))
    )
    (net (code "132") (name "unconnected-(U$2-PadP$19)") (class "Default")
      (node (ref "U$2") (pin "P$19") (pinfunction "P$19_P$19") (pintype "bidirectional"))
    )
    (net (code "133") (name "unconnected-(U$2-PadP$20)") (class "Default")
      (node (ref "U$2") (pin "P$20") (pinfunction "P$20_P$20") (pintype "bidirectional"))
    )
    (net (code "134") (name "unconnected-(U$2-PadP$21)") (class "Default")
      (node (ref "U$2") (pin "P$21") (pinfunction "P$21_P$21") (pintype "bidirectional"))
    )
    (net (code "135") (name "unconnected-(U$2-PadP$22)") (class "Default")
      (node (ref "U$2") (pin "P$22") (pinfunction "P$22_P$22") (pintype "bidirectional"))
    )
    (net (code "136") (name "unconnected-(U$2-PadP$23)") (class "Default")
      (node (ref "U$2") (pin "P$23") (pinfunction "P$23_P$23") (pintype "bidirectional"))
    )
    (net (code "137") (name "unconnected-(U$2-PadP$24)") (class "Default")
      (node (ref "U$2") (pin "P$24") (pinfunction "P$24_P$24") (pintype "bidirectional"))
    )
    (net (code "138") (name "unconnected-(U$2-PadP$25)") (class "Default")
      (node (ref "U$2") (pin "P$25") (pinfunction "P$25_P$25") (pintype "bidirectional"))
    )
    (net (code "139") (name "unconnected-(U$2-PadP$26)") (class "Default")
      (node (ref "U$2") (pin "P$26") (pinfunction "P$26_P$26") (pintype "bidirectional"))
    )
    (net (code "140") (name "unconnected-(U$2-PadP$27)") (class "Default")
      (node (ref "U$2") (pin "P$27") (pinfunction "P$27_P$27") (pintype "bidirectional"))
    )
    (net (code "141") (name "unconnected-(U$2-PadP$28)") (class "Default")
      (node (ref "U$2") (pin "P$28") (pinfunction "P$28_P$28") (pintype "bidirectional"))
    )
    (net (code "142") (name "unconnected-(U$2-PadP$29)") (class "Default")
      (node (ref "U$2") (pin "P$29") (pinfunction "P$29_P$29") (pintype "bidirectional"))
    )
    (net (code "143") (name "unconnected-(U$2-PadP$30)") (class "Default")
      (node (ref "U$2") (pin "P$30") (pinfunction "P$30_P$30") (pintype "bidirectional"))
    )
    (net (code "144") (name "unconnected-(U$2-PadP$31)") (class "Default")
      (node (ref "U$2") (pin "P$31") (pinfunction "P$31_P$31") (pintype "bidirectional"))
    )
    (net (code "145") (name "unconnected-(U$2-PadP$32)") (class "Default")
      (node (ref "U$2") (pin "P$32") (pinfunction "P$32_P$32") (pintype "bidirectional"))
    )
    (net (code "146") (name "unconnected-(U$2-PadP$33)") (class "Default")
      (node (ref "U$2") (pin "P$33") (pinfunction "P$33_P$33") (pintype "bidirectional"))
    )
    (net (code "147") (name "unconnected-(U$2-PadP$34)") (class "Default")
      (node (ref "U$2") (pin "P$34") (pinfunction "P$34_P$34") (pintype "bidirectional"))
    )
    (net (code "148") (name "unconnected-(U$2-PadP$35)") (class "Default")
      (node (ref "U$2") (pin "P$35") (pinfunction "P$35_P$35") (pintype "bidirectional"))
    )
    (net (code "149") (name "unconnected-(U$2-PadP$36)") (class "Default")
      (node (ref "U$2") (pin "P$36") (pinfunction "P$36_P$36") (pintype "bidirectional"))
    )
    (net (code "150") (name "unconnected-(U$2-PadP$37)") (class "Default")
      (node (ref "U$2") (pin "P$37") (pinfunction "P$37_P$37") (pintype "bidirectional"))
    )
    (net (code "151") (name "unconnected-(U$2-PadP$38)") (class "Default")
      (node (ref "U$2") (pin "P$38") (pinfunction "P$38_P$38") (pintype "bidirectional"))
    )
    (net (code "152") (name "unconnected-(U$2-PadP$39)") (class "Default")
      (node (ref "U$2") (pin "P$39") (pinfunction "P$39_P$39") (pintype "bidirectional"))
    )
    (net (code "153") (name "unconnected-(U$2-PadP$40)") (class "Default")
      (node (ref "U$2") (pin "P$40") (pinfunction "P$40_P$40") (pintype "bidirectional"))
    )
    (net (code "154") (name "unconnected-(U$2-PadP$41)") (class "Default")
      (node (ref "U$2") (pin "P$41") (pinfunction "P$41_P$41") (pintype "bidirectional"))
    )
    (net (code "155") (name "unconnected-(U$2-PadP$42)") (class "Default")
      (node (ref "U$2") (pin "P$42") (pinfunction "P$42_P$42") (pintype "bidirectional"))
    )
    (net (code "156") (name "unconnected-(U$2-PadP$43)") (class "Default")
      (node (ref "U$2") (pin "P$43") (pinfunction "P$43_P$43") (pintype "bidirectional"))
    )
    (net (code "157") (name "unconnected-(U$2-PadP$44)") (class "Default")
      (node (ref "U$2") (pin "P$44") (pinfunction "P$44_P$44") (pintype "bidirectional"))
    )
    (net (code "158") (name "unconnected-(U$2-PadP$45)") (class "Default")
      (node (ref "U$2") (pin "P$45") (pinfunction "P$45_P$45") (pintype "bidirectional"))
    )
    (net (code "159") (name "unconnected-(U$2-PadP$46)") (class "Default")
      (node (ref "U$2") (pin "P$46") (pinfunction "P$46_P$46") (pintype "bidirectional"))
    )
    (net (code "160") (name "unconnected-(U$2-PadP$47)") (class "Default")
      (node (ref "U$2") (pin "P$47") (pinfunction "P$47_P$47") (pintype "bidirectional"))
    )
    (net (code "161") (name "unconnected-(U$2-PadP$48)") (class "Default")
      (node (ref "U$2") (pin "P$48") (pinfunction "P$48_P$48") (pintype "bidirectional"))
    )
    (net (code "162") (name "unconnected-(U$2-PadP$49)") (class "Default")
      (node (ref "U$2") (pin "P$49") (pinfunction "P$49_P$49") (pintype "bidirectional"))
    )
    (net (code "163") (name "unconnected-(U$2-PadP$50)") (class "Default")
      (node (ref "U$2") (pin "P$50") (pinfunction "P$50_P$50") (pintype "bidirectional"))
    )
    (net (code "164") (name "unconnected-(U$2-PadP$51)") (class "Default")
      (node (ref "U$2") (pin "P$51") (pinfunction "P$51_P$51") (pintype "bidirectional"))
    )
    (net (code "165") (name "unconnected-(U$2-PadP$52)") (class "Default")
      (node (ref "U$2") (pin "P$52") (pinfunction "P$52_P$52") (pintype "bidirectional"))
    )
    (net (code "166") (name "unconnected-(U$2-PadP$53)") (class "Default")
      (node (ref "U$2") (pin "P$53") (pinfunction "P$53_P$53") (pintype "bidirectional"))
    )
    (net (code "167") (name "unconnected-(U$2-PadP$54)") (class "Default")
      (node (ref "U$2") (pin "P$54") (pinfunction "P$54_P$54") (pintype "bidirectional"))
    )
    (net (code "168") (name "unconnected-(U$2-PadP$55)") (class "Default")
      (node (ref "U$2") (pin "P$55") (pinfunction "P$55_P$55") (pintype "bidirectional"))
    )
    (net (code "169") (name "unconnected-(U$2-PadP$56)") (class "Default")
      (node (ref "U$2") (pin "P$56") (pinfunction "P$56_P$56") (pintype "bidirectional"))
    )
    (net (code "170") (name "unconnected-(U$2-PadP$57)") (class "Default")
      (node (ref "U$2") (pin "P$57") (pinfunction "P$57_P$57") (pintype "bidirectional"))
    )
    (net (code "171") (name "unconnected-(U$2-PadP$58)") (class "Default")
      (node (ref "U$2") (pin "P$58") (pinfunction "P$58_P$58") (pintype "bidirectional"))
    )
    (net (code "172") (name "unconnected-(U$2-PadP$59)") (class "Default")
      (node (ref "U$2") (pin "P$59") (pinfunction "P$59_P$59") (pintype "bidirectional"))
    )
    (net (code "173") (name "unconnected-(U$2-PadP$60)") (class "Default")
      (node (ref "U$2") (pin "P$60") (pinfunction "P$60_P$60") (pintype "bidirectional"))
    )
    (net (code "174") (name "unconnected-(U$2-PadP$61)") (class "Default")
      (node (ref "U$2") (pin "P$61") (pinfunction "P$61_P$61") (pintype "bidirectional"))
    )
    (net (code "175") (name "unconnected-(U$2-PadP$62)") (class "Default")
      (node (ref "U$2") (pin "P$62") (pinfunction "P$62_P$62") (pintype "bidirectional"))
    )
    (net (code "176") (name "unconnected-(U$2-PadP$63)") (class "Default")
      (node (ref "U$2") (pin "P$63") (pinfunction "P$63_P$63") (pintype "bidirectional"))
    )
    (net (code "177") (name "unconnected-(U$2-PadP$64)") (class "Default")
      (node (ref "U$2") (pin "P$64") (pinfunction "P$64_P$64") (pintype "bidirectional"))
    )
    (net (code "178") (name "unconnected-(U$2-PadP$65)") (class "Default")
      (node (ref "U$2") (pin "P$65") (pinfunction "P$65_P$65") (pintype "bidirectional"))
    )
    (net (code "179") (name "unconnected-(U$2-PadP$66)") (class "Default")
      (node (ref "U$2") (pin "P$66") (pinfunction "P$66_P$66") (pintype "bidirectional"))
    )
    (net (code "180") (name "unconnected-(U$2-PadP$67)") (class "Default")
      (node (ref "U$2") (pin "P$67") (pinfunction "P$67_P$67") (pintype "bidirectional"))
    )
    (net (code "181") (name "unconnected-(U$2-PadP$68)") (class "Default")
      (node (ref "U$2") (pin "P$68") (pinfunction "P$68_P$68") (pintype "bidirectional"))
    )
    (net (code "182") (name "unconnected-(U$2-PadP$69)") (class "Default")
      (node (ref "U$2") (pin "P$69") (pinfunction "P$69_P$69") (pintype "bidirectional"))
    )
    (net (code "183") (name "unconnected-(U$2-PadP$70)") (class "Default")
      (node (ref "U$2") (pin "P$70") (pinfunction "P$70_P$70") (pintype "bidirectional"))
    )
    (net (code "184") (name "unconnected-(U$2-PadP$71)") (class "Default")
      (node (ref "U$2") (pin "P$71") (pinfunction "P$71_P$71") (pintype "bidirectional"))
    )
    (net (code "185") (name "unconnected-(U$2-PadP$72)") (class "Default")
      (node (ref "U$2") (pin "P$72") (pinfunction "P$72_P$72") (pintype "bidirectional"))
    )
    (net (code "186") (name "unconnected-(U$2-PadP$73)") (class "Default")
      (node (ref "U$2") (pin "P$73") (pinfunction "P$73_P$73") (pintype "bidirectional"))
    )
    (net (code "187") (name "unconnected-(U$2-PadP$74)") (class "Default")
      (node (ref "U$2") (pin "P$74") (pinfunction "P$74_P$74") (pintype "bidirectional"))
    )
    (net (code "188") (name "unconnected-(U$2-PadP$75)") (class "Default")
      (node (ref "U$2") (pin "P$75") (pinfunction "P$75_P$75") (pintype "bidirectional"))
    )
    (net (code "189") (name "unconnected-(U$2-PadP$76)") (class "Default")
      (node (ref "U$2") (pin "P$76") (pinfunction "P$76_P$76") (pintype "bidirectional"))
    )
    (net (code "190") (name "unconnected-(U$2-PadP$77)") (class "Default")
      (node (ref "U$2") (pin "P$77") (pinfunction "P$77_P$77") (pintype "bidirectional"))
    )
    (net (code "191") (name "unconnected-(U$2-PadP$78)") (class "Default")
      (node (ref "U$2") (pin "P$78") (pinfunction "P$78_P$78") (pintype "bidirectional"))
    )
    (net (code "192") (name "unconnected-(U$2-PadP$79)") (class "Default")
      (node (ref "U$2") (pin "P$79") (pinfunction "P$79_P$79") (pintype "bidirectional"))
    )
    (net (code "193") (name "unconnected-(U$2-PadP$80)") (class "Default")
      (node (ref "U$2") (pin "P$80") (pinfunction "P$80_P$80") (pintype "bidirectional"))
    )
    (net (code "194") (name "unconnected-(U$2-PadP$81)") (class "Default")
      (node (ref "U$2") (pin "P$81") (pinfunction "P$81_P$81") (pintype "bidirectional"))
    )
    (net (code "195") (name "unconnected-(U$2-PadP$82)") (class "Default")
      (node (ref "U$2") (pin "P$82") (pinfunction "P$82_P$82") (pintype "bidirectional"))
    )
    (net (code "196") (name "unconnected-(U$2-PadP$83)") (class "Default")
      (node (ref "U$2") (pin "P$83") (pinfunction "P$83_P$83") (pintype "bidirectional"))
    )
    (net (code "197") (name "unconnected-(U$2-PadP$84)") (class "Default")
      (node (ref "U$2") (pin "P$84") (pinfunction "P$84_P$84") (pintype "bidirectional"))
    )
    (net (code "198") (name "unconnected-(U$2-PadP$85)") (class "Default")
      (node (ref "U$2") (pin "P$85") (pinfunction "P$85_P$85") (pintype "bidirectional"))
    )
    (net (code "199") (name "unconnected-(U$2-PadP$86)") (class "Default")
      (node (ref "U$2") (pin "P$86") (pinfunction "P$86_P$86") (pintype "bidirectional"))
    )
    (net (code "200") (name "unconnected-(U$2-PadP$87)") (class "Default")
      (node (ref "U$2") (pin "P$87") (pinfunction "P$87_P$87") (pintype "bidirectional"))
    )
    (net (code "201") (name "unconnected-(U$2-PadP$88)") (class "Default")
      (node (ref "U$2") (pin "P$88") (pinfunction "P$88_P$88") (pintype "bidirectional"))
    )
    (net (code "202") (name "unconnected-(U$2-PadP$89)") (class "Default")
      (node (ref "U$2") (pin "P$89") (pinfunction "P$89_P$89") (pintype "bidirectional"))
    )
    (net (code "203") (name "unconnected-(U$2-PadP$90)") (class "Default")
      (node (ref "U$2") (pin "P$90") (pinfunction "P$90_P$90") (pintype "bidirectional"))
    )
    (net (code "204") (name "unconnected-(U$2-PadP$91)") (class "Default")
      (node (ref "U$2") (pin "P$91") (pinfunction "P$91_P$91") (pintype "bidirectional"))
    )
    (net (code "205") (name "unconnected-(U$2-PadP$92)") (class "Default")
      (node (ref "U$2") (pin "P$92") (pinfunction "P$92_P$92") (pintype "bidirectional"))
    )
    (net (code "206") (name "unconnected-(U$2-PadP$93)") (class "Default")
      (node (ref "U$2") (pin "P$93") (pinfunction "P$93_P$93") (pintype "bidirectional"))
    )
    (net (code "207") (name "unconnected-(U$2-PadP$94)") (class "Default")
      (node (ref "U$2") (pin "P$94") (pinfunction "P$94_P$94") (pintype "bidirectional"))
    )
    (net (code "208") (name "unconnected-(U$2-PadP$95)") (class "Default")
      (node (ref "U$2") (pin "P$95") (pinfunction "P$95_P$95") (pintype "bidirectional"))
    )
    (net (code "209") (name "unconnected-(U$2-PadP$96)") (class "Default")
      (node (ref "U$2") (pin "P$96") (pinfunction "P$96_P$96") (pintype "bidirectional"))
    )
    (net (code "210") (name "unconnected-(U$2-PadP$97)") (class "Default")
      (node (ref "U$2") (pin "P$97") (pinfunction "P$97_P$97") (pintype "bidirectional"))
    )
    (net (code "211") (name "unconnected-(U$2-PadP$98)") (class "Default")
      (node (ref "U$2") (pin "P$98") (pinfunction "P$98_P$98") (pintype "bidirectional"))
    )
    (net (code "212") (name "unconnected-(U$2-PadP$99)") (class "Default")
      (node (ref "U$2") (pin "P$99") (pinfunction "P$99_P$99") (pintype "bidirectional"))
    )
    (net (code "213") (name "unconnected-(U$2-PadP$100)") (class "Default")
      (node (ref "U$2") (pin "P$100") (pinfunction "P$100_P$100") (pintype "bidirectional"))
    )
    (net (code "214") (name "unconnected-(U$2-PadP$101)") (class "Default")
      (node (ref "U$2") (pin "P$101") (pinfunction "P$101_P$101") (pintype "bidirectional"))
    )
    (net (code "215") (name "unconnected-(U$2-PadP$102)") (class "Default")
      (node (ref "U$2") (pin "P$102") (pinfunction "P$102_P$102") (pintype "bidirectional"))
    )
    (net (code "216") (name "unconnected-(U$2-PadP$103)") (class "Default")
      (node (ref "U$2") (pin "P$103") (pinfunction "P$103_P$103") (pintype "bidirectional"))
    )
    (net (code "217") (name "unconnected-(U$2-PadP$104)") (class "Default")
      (node (ref "U$2") (pin "P$104") (pinfunction "P$104_P$104") (pintype "bidirectional"))
    )
    (net (code "218") (name "unconnected-(U$2-PadP$105)") (class "Default")
      (node (ref "U$2") (pin "P$105") (pinfunction "P$105_P$105") (pintype "bidirectional"))
    )
    (net (code "219") (name "unconnected-(U$2-PadP$106)") (class "Default")
      (node (ref "U$2") (pin "P$106") (pinfunction "P$106_P$106") (pintype "bidirectional"))
    )
    (net (code "220") (name "unconnected-(U$2-PadP$107)") (class "Default")
      (node (ref "U$2") (pin "P$107") (pinfunction "P$107_P$107") (pintype "bidirectional"))
    )
    (net (code "221") (name "unconnected-(U$2-PadP$108)") (class "Default")
      (node (ref "U$2") (pin "P$108") (pinfunction "P$108_P$108") (pintype "bidirectional"))
    )
    (net (code "222") (name "unconnected-(U$2-PadP$109)") (class "Default")
      (node (ref "U$2") (pin "P$109") (pinfunction "P$109_P$109") (pintype "bidirectional"))
    )
    (net (code "223") (name "unconnected-(U$2-PadP$110)") (class "Default")
      (node (ref "U$2") (pin "P$110") (pinfunction "P$110_P$110") (pintype "bidirectional"))
    )
    (net (code "224") (name "unconnected-(U$2-PadP$111)") (class "Default")
      (node (ref "U$2") (pin "P$111") (pinfunction "P$111_P$111") (pintype "bidirectional"))
    )
    (net (code "225") (name "unconnected-(U$2-PadP$112)") (class "Default")
      (node (ref "U$2") (pin "P$112") (pinfunction "P$112_P$112") (pintype "bidirectional"))
    )
    (net (code "226") (name "unconnected-(U$2-PadP$113)") (class "Default")
      (node (ref "U$2") (pin "P$113") (pinfunction "P$113_P$113") (pintype "bidirectional"))
    )
    (net (code "227") (name "unconnected-(U$2-PadP$114)") (class "Default")
      (node (ref "U$2") (pin "P$114") (pinfunction "P$114_P$114") (pintype "bidirectional"))
    )
    (net (code "228") (name "unconnected-(U$2-PadP$115)") (class "Default")
      (node (ref "U$2") (pin "P$115") (pinfunction "P$115_P$115") (pintype "bidirectional"))
    )
    (net (code "229") (name "unconnected-(U$2-PadP$116)") (class "Default")
      (node (ref "U$2") (pin "P$116") (pinfunction "P$116_P$116") (pintype "bidirectional"))
    )
    (net (code "230") (name "unconnected-(U$2-PadP$117)") (class "Default")
      (node (ref "U$2") (pin "P$117") (pinfunction "P$117_P$117") (pintype "bidirectional"))
    )
    (net (code "231") (name "unconnected-(U$2-PadP$118)") (class "Default")
      (node (ref "U$2") (pin "P$118") (pinfunction "P$118_P$118") (pintype "bidirectional"))
    )
    (net (code "232") (name "unconnected-(U$2-PadP$119)") (class "Default")
      (node (ref "U$2") (pin "P$119") (pinfunction "P$119_P$119") (pintype "bidirectional"))
    )
    (net (code "233") (name "unconnected-(U$2-PadP$120)") (class "Default")
      (node (ref "U$2") (pin "P$120") (pinfunction "P$120_P$120") (pintype "bidirectional"))
    )
    (net (code "234") (name "unconnected-(U$2-PadP$121)") (class "Default")
      (node (ref "U$2") (pin "P$121") (pinfunction "P$121_P$121") (pintype "bidirectional"))
    )
    (net (code "235") (name "unconnected-(U$2-PadP$122)") (class "Default")
      (node (ref "U$2") (pin "P$122") (pinfunction "P$122_P$122") (pintype "bidirectional"))
    )
    (net (code "236") (name "unconnected-(U$2-PadP$123)") (class "Default")
      (node (ref "U$2") (pin "P$123") (pinfunction "P$123_P$123") (pintype "bidirectional"))
    )
    (net (code "237") (name "unconnected-(U$2-PadP$124)") (class "Default")
      (node (ref "U$2") (pin "P$124") (pinfunction "P$124_P$124") (pintype "bidirectional"))
    )
    (net (code "238") (name "unconnected-(U$2-PadP$125)") (class "Default")
      (node (ref "U$2") (pin "P$125") (pinfunction "P$125_P$125") (pintype "bidirectional"))
    )
    (net (code "239") (name "unconnected-(U$2-PadP$126)") (class "Default")
      (node (ref "U$2") (pin "P$126") (pinfunction "P$126_P$126") (pintype "bidirectional"))
    )
    (net (code "240") (name "unconnected-(U$2-PadP$127)") (class "Default")
      (node (ref "U$2") (pin "P$127") (pinfunction "P$127_P$127") (pintype "bidirectional"))
    )
    (net (code "241") (name "unconnected-(U$2-PadP$128)") (class "Default")
      (node (ref "U$2") (pin "P$128") (pinfunction "P$128_P$128") (pintype "bidirectional"))
    )
    (net (code "242") (name "unconnected-(U$2-PadP$129)") (class "Default")
      (node (ref "U$2") (pin "P$129") (pinfunction "P$129_P$129") (pintype "bidirectional"))
    )
    (net (code "243") (name "unconnected-(U$2-PadP$130)") (class "Default")
      (node (ref "U$2") (pin "P$130") (pinfunction "P$130_P$130") (pintype "bidirectional"))
    )
    (net (code "244") (name "unconnected-(U$2-PadP$131)") (class "Default")
      (node (ref "U$2") (pin "P$131") (pinfunction "P$131_P$131") (pintype "bidirectional"))
    )
    (net (code "245") (name "unconnected-(U$2-PadP$132)") (class "Default")
      (node (ref "U$2") (pin "P$132") (pinfunction "P$132_P$132") (pintype "bidirectional"))
    )
    (net (code "246") (name "unconnected-(U$2-PadP$133)") (class "Default")
      (node (ref "U$2") (pin "P$133") (pinfunction "P$133_P$133") (pintype "bidirectional"))
    )
    (net (code "247") (name "unconnected-(U$2-PadP$134)") (class "Default")
      (node (ref "U$2") (pin "P$134") (pinfunction "P$134_P$134") (pintype "bidirectional"))
    )
    (net (code "248") (name "unconnected-(U$2-PadP$135)") (class "Default")
      (node (ref "U$2") (pin "P$135") (pinfunction "P$135_P$135") (pintype "bidirectional"))
    )
    (net (code "249") (name "unconnected-(U$2-PadP$136)") (class "Default")
      (node (ref "U$2") (pin "P$136") (pinfunction "P$136_P$136") (pintype "bidirectional"))
    )
    (net (code "250") (name "unconnected-(U$2-PadP$137)") (class "Default")
      (node (ref "U$2") (pin "P$137") (pinfunction "P$137_P$137") (pintype "bidirectional"))
    )
    (net (code "251") (name "unconnected-(U$2-PadP$138)") (class "Default")
      (node (ref "U$2") (pin "P$138") (pinfunction "P$138_P$138") (pintype "bidirectional"))
    )
    (net (code "252") (name "unconnected-(U$2-PadP$139)") (class "Default")
      (node (ref "U$2") (pin "P$139") (pinfunction "P$139_P$139") (pintype "bidirectional"))
    )
    (net (code "253") (name "unconnected-(U$2-PadP$140)") (class "Default")
      (node (ref "U$2") (pin "P$140") (pinfunction "P$140_P$140") (pintype "bidirectional"))
    )
    (net (code "254") (name "unconnected-(U$2-PadP$141)") (class "Default")
      (node (ref "U$2") (pin "P$141") (pinfunction "P$141_P$141") (pintype "bidirectional"))
    )
    (net (code "255") (name "unconnected-(U$2-PadP$142)") (class "Default")
      (node (ref "U$2") (pin "P$142") (pinfunction "P$142_P$142") (pintype "bidirectional"))
    )
    (net (code "256") (name "unconnected-(U$2-PadP$143)") (class "Default")
      (node (ref "U$2") (pin "P$143") (pinfunction "P$143_P$143") (pintype "bidirectional"))
    )
    (net (code "257") (name "unconnected-(U$2-PadP$144)") (class "Default")
      (node (ref "U$2") (pin "P$144") (pinfunction "P$144_P$144") (pintype "bidirectional"))
    )
    (net (code "258") (name "unconnected-(U$2-PadP$145)") (class "Default")
      (node (ref "U$2") (pin "P$145") (pinfunction "P$145_P$145") (pintype "bidirectional"))
    )
    (net (code "259") (name "unconnected-(U$2-PadP$146)") (class "Default")
      (node (ref "U$2") (pin "P$146") (pinfunction "P$146_P$146") (pintype "bidirectional"))
    )
    (net (code "260") (name "unconnected-(U$2-PadP$147)") (class "Default")
      (node (ref "U$2") (pin "P$147") (pinfunction "P$147_P$147") (pintype "bidirectional"))
    )
    (net (code "261") (name "unconnected-(U$2-PadP$148)") (class "Default")
      (node (ref "U$2") (pin "P$148") (pinfunction "P$148_P$148") (pintype "bidirectional"))
    )
    (net (code "262") (name "unconnected-(U$2-PadP$149)") (class "Default")
      (node (ref "U$2") (pin "P$149") (pinfunction "P$149_P$149") (pintype "bidirectional"))
    )
    (net (code "263") (name "unconnected-(U$2-PadP$150)") (class "Default")
      (node (ref "U$2") (pin "P$150") (pinfunction "P$150_P$150") (pintype "bidirectional"))
    )
    (net (code "264") (name "unconnected-(U$2-PadP$151)") (class "Default")
      (node (ref "U$2") (pin "P$151") (pinfunction "P$151_P$151") (pintype "bidirectional"))
    )
    (net (code "265") (name "unconnected-(U$2-PadP$152)") (class "Default")
      (node (ref "U$2") (pin "P$152") (pinfunction "P$152_P$152") (pintype "bidirectional"))
    )
    (net (code "266") (name "unconnected-(U$2-PadP$153)") (class "Default")
      (node (ref "U$2") (pin "P$153") (pinfunction "P$153_P$153") (pintype "bidirectional"))
    )
    (net (code "267") (name "unconnected-(U$2-PadP$154)") (class "Default")
      (node (ref "U$2") (pin "P$154") (pinfunction "P$154_P$154") (pintype "bidirectional"))
    )
    (net (code "268") (name "unconnected-(U$2-PadP$155)") (class "Default")
      (node (ref "U$2") (pin "P$155") (pinfunction "P$155_P$155") (pintype "bidirectional"))
    )
    (net (code "269") (name "unconnected-(U$2-PadP$156)") (class "Default")
      (node (ref "U$2") (pin "P$156") (pinfunction "P$156_P$156") (pintype "bidirectional"))
    )
    (net (code "270") (name "unconnected-(U$2-PadP$157)") (class "Default")
      (node (ref "U$2") (pin "P$157") (pinfunction "P$157_P$157") (pintype "bidirectional"))
    )
    (net (code "271") (name "unconnected-(U$2-PadP$158)") (class "Default")
      (node (ref "U$2") (pin "P$158") (pinfunction "P$158_P$158") (pintype "bidirectional"))
    )
    (net (code "272") (name "unconnected-(U$2-PadP$159)") (class "Default")
      (node (ref "U$2") (pin "P$159") (pinfunction "P$159_P$159") (pintype "bidirectional"))
    )
    (net (code "273") (name "unconnected-(U$2-PadP$160)") (class "Default")
      (node (ref "U$2") (pin "P$160") (pinfunction "P$160_P$160") (pintype "bidirectional"))
    )
    (net (code "274") (name "unconnected-(U$2-PadP$161)") (class "Default")
      (node (ref "U$2") (pin "P$161") (pinfunction "P$161_P$161") (pintype "bidirectional"))
    )
    (net (code "275") (name "unconnected-(U$2-PadP$162)") (class "Default")
      (node (ref "U$2") (pin "P$162") (pinfunction "P$162_P$162") (pintype "bidirectional"))
    )
    (net (code "276") (name "unconnected-(U$2-PadP$163)") (class "Default")
      (node (ref "U$2") (pin "P$163") (pinfunction "P$163_P$163") (pintype "bidirectional"))
    )
    (net (code "277") (name "unconnected-(U$2-PadP$164)") (class "Default")
      (node (ref "U$2") (pin "P$164") (pinfunction "P$164_P$164") (pintype "bidirectional"))
    )
    (net (code "278") (name "unconnected-(U$2-PadP$165)") (class "Default")
      (node (ref "U$2") (pin "P$165") (pinfunction "P$165_P$165") (pintype "bidirectional"))
    )
    (net (code "279") (name "unconnected-(U$2-PadP$166)") (class "Default")
      (node (ref "U$2") (pin "P$166") (pinfunction "P$166_P$166") (pintype "bidirectional"))
    )
    (net (code "280") (name "unconnected-(U$2-PadP$167)") (class "Default")
      (node (ref "U$2") (pin "P$167") (pinfunction "P$167_P$167") (pintype "bidirectional"))
    )
    (net (code "281") (name "unconnected-(U$2-PadP$168)") (class "Default")
      (node (ref "U$2") (pin "P$168") (pinfunction "P$168_P$168") (pintype "bidirectional"))
    )
    (net (code "282") (name "unconnected-(U$2-PadP$169)") (class "Default")
      (node (ref "U$2") (pin "P$169") (pinfunction "P$169_P$169") (pintype "bidirectional"))
    )
    (net (code "283") (name "unconnected-(U$2-PadP$170)") (class "Default")
      (node (ref "U$2") (pin "P$170") (pinfunction "P$170_P$170") (pintype "bidirectional"))
    )
    (net (code "284") (name "unconnected-(U$2-PadP$171)") (class "Default")
      (node (ref "U$2") (pin "P$171") (pinfunction "P$171_P$171") (pintype "bidirectional"))
    )
    (net (code "285") (name "unconnected-(U$2-PadP$172)") (class "Default")
      (node (ref "U$2") (pin "P$172") (pinfunction "P$172_P$172") (pintype "bidirectional"))
    )
    (net (code "286") (name "unconnected-(U$2-PadP$173)") (class "Default")
      (node (ref "U$2") (pin "P$173") (pinfunction "P$173_P$173") (pintype "bidirectional"))
    )
    (net (code "287") (name "unconnected-(U$2-PadP$174)") (class "Default")
      (node (ref "U$2") (pin "P$174") (pinfunction "P$174_P$174") (pintype "bidirectional"))
    )
    (net (code "288") (name "unconnected-(U$2-PadP$175)") (class "Default")
      (node (ref "U$2") (pin "P$175") (pinfunction "P$175_P$175") (pintype "bidirectional"))
    )
    (net (code "289") (name "unconnected-(U$2-PadP$176)") (class "Default")
      (node (ref "U$2") (pin "P$176") (pinfunction "P$176_P$176") (pintype "bidirectional"))
    )
    (net (code "290") (name "unconnected-(U$2-PadP$177)") (class "Default")
      (node (ref "U$2") (pin "P$177") (pinfunction "P$177_P$177") (pintype "bidirectional"))
    )
    (net (code "291") (name "unconnected-(U$2-PadP$178)") (class "Default")
      (node (ref "U$2") (pin "P$178") (pinfunction "P$178_P$178") (pintype "bidirectional"))
    )
    (net (code "292") (name "unconnected-(U$2-PadP$179)") (class "Default")
      (node (ref "U$2") (pin "P$179") (pinfunction "P$179_P$179") (pintype "bidirectional"))
    )
    (net (code "293") (name "unconnected-(U$2-PadP$180)") (class "Default")
      (node (ref "U$2") (pin "P$180") (pinfunction "P$180_P$180") (pintype "bidirectional"))
    )
    (net (code "294") (name "unconnected-(U$2-PadP$181)") (class "Default")
      (node (ref "U$2") (pin "P$181") (pinfunction "P$181_P$181") (pintype "bidirectional"))
    )
    (net (code "295") (name "unconnected-(U$2-PadP$182)") (class "Default")
      (node (ref "U$2") (pin "P$182") (pinfunction "P$182_P$182") (pintype "bidirectional"))
    )
  )
)
